# axiom_beta_sensor_cmv12000_tht_v0_16_r1_.net
KiCad netlist of a schematic drawn in EAGLE
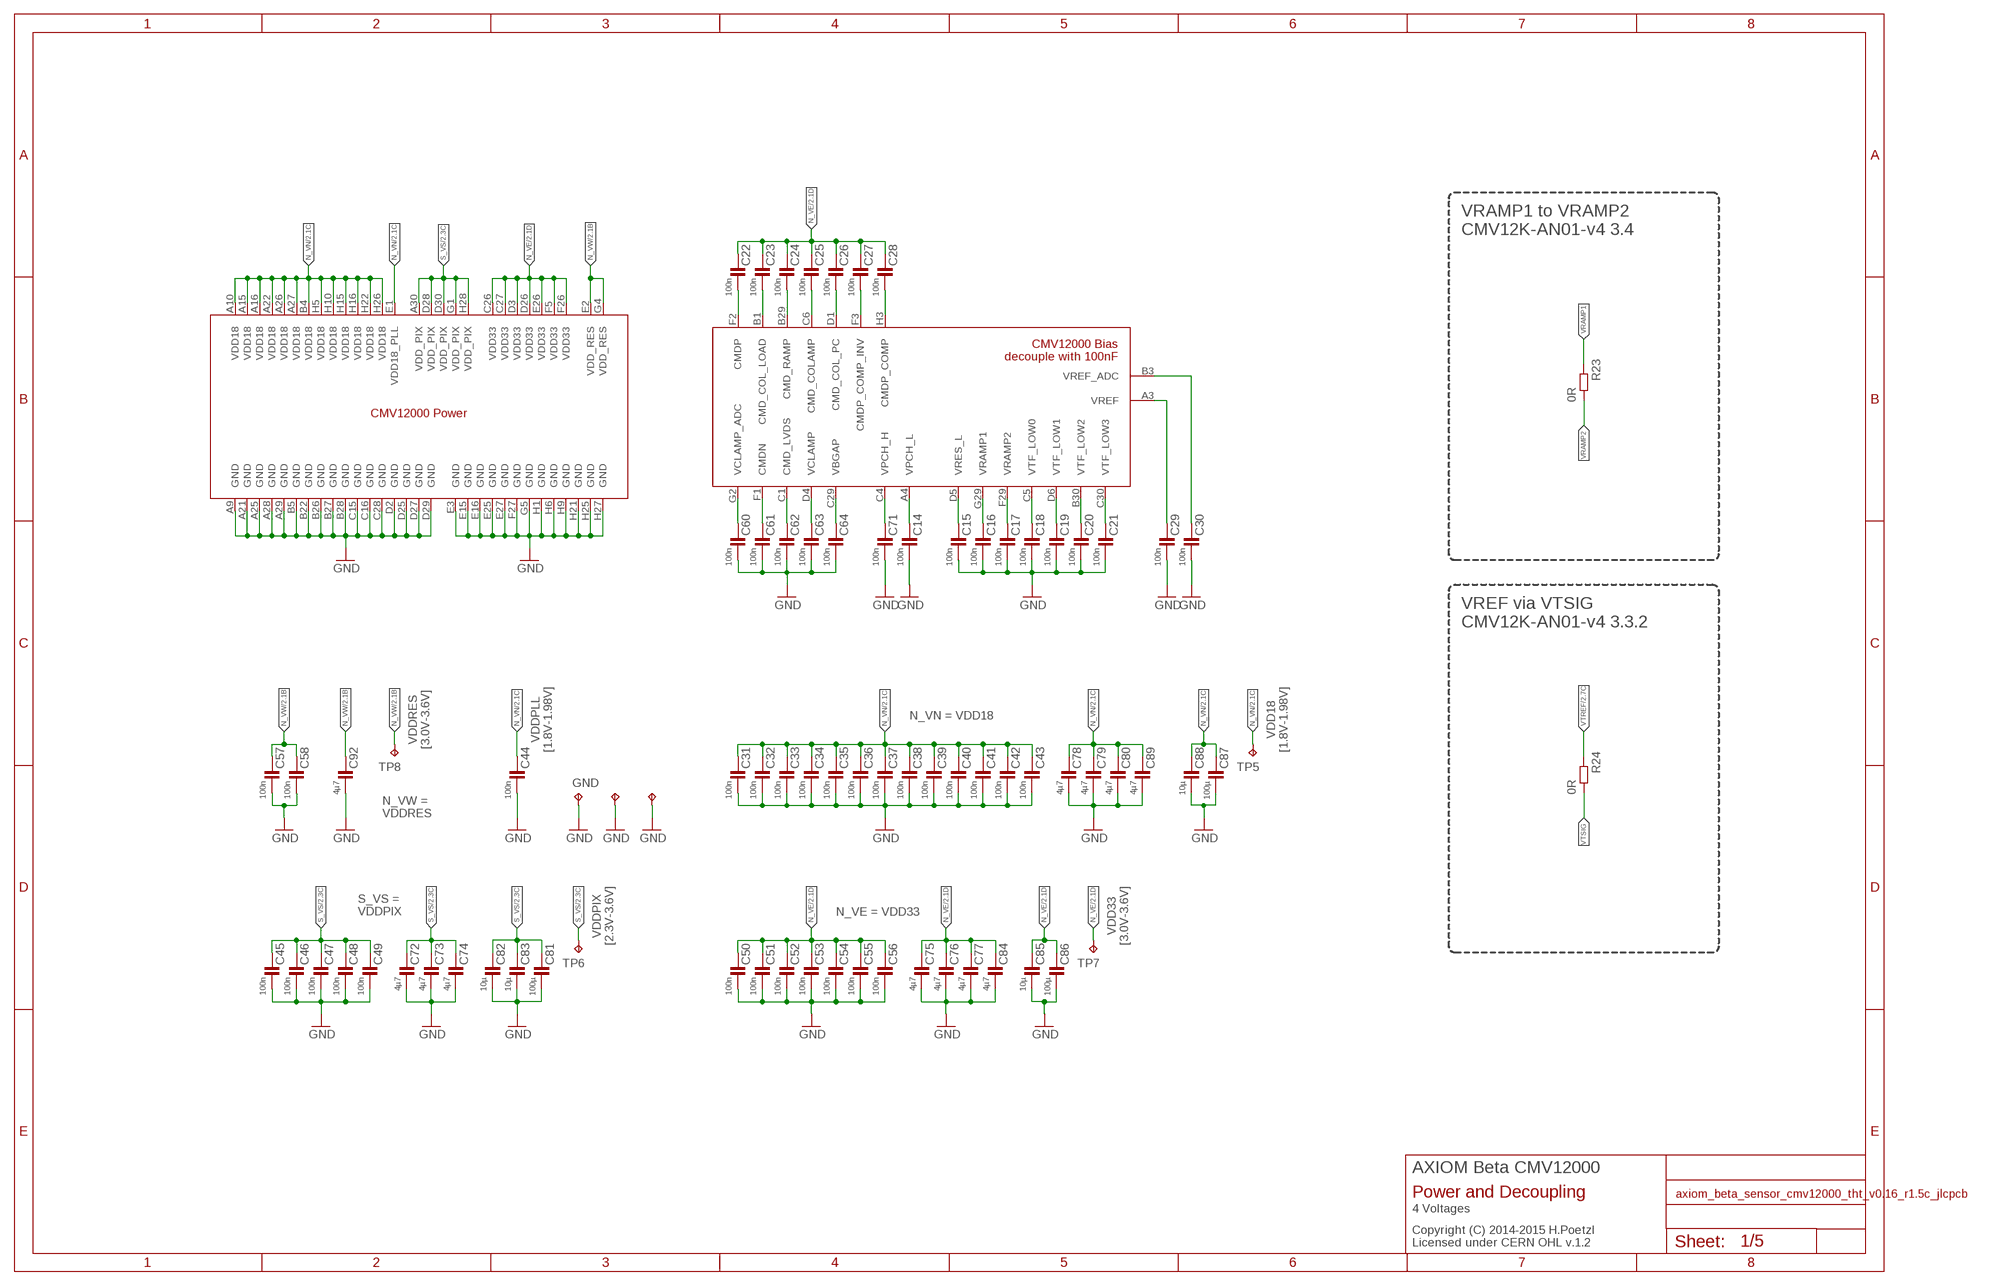
[diagram p0: schematic, sheet 1]
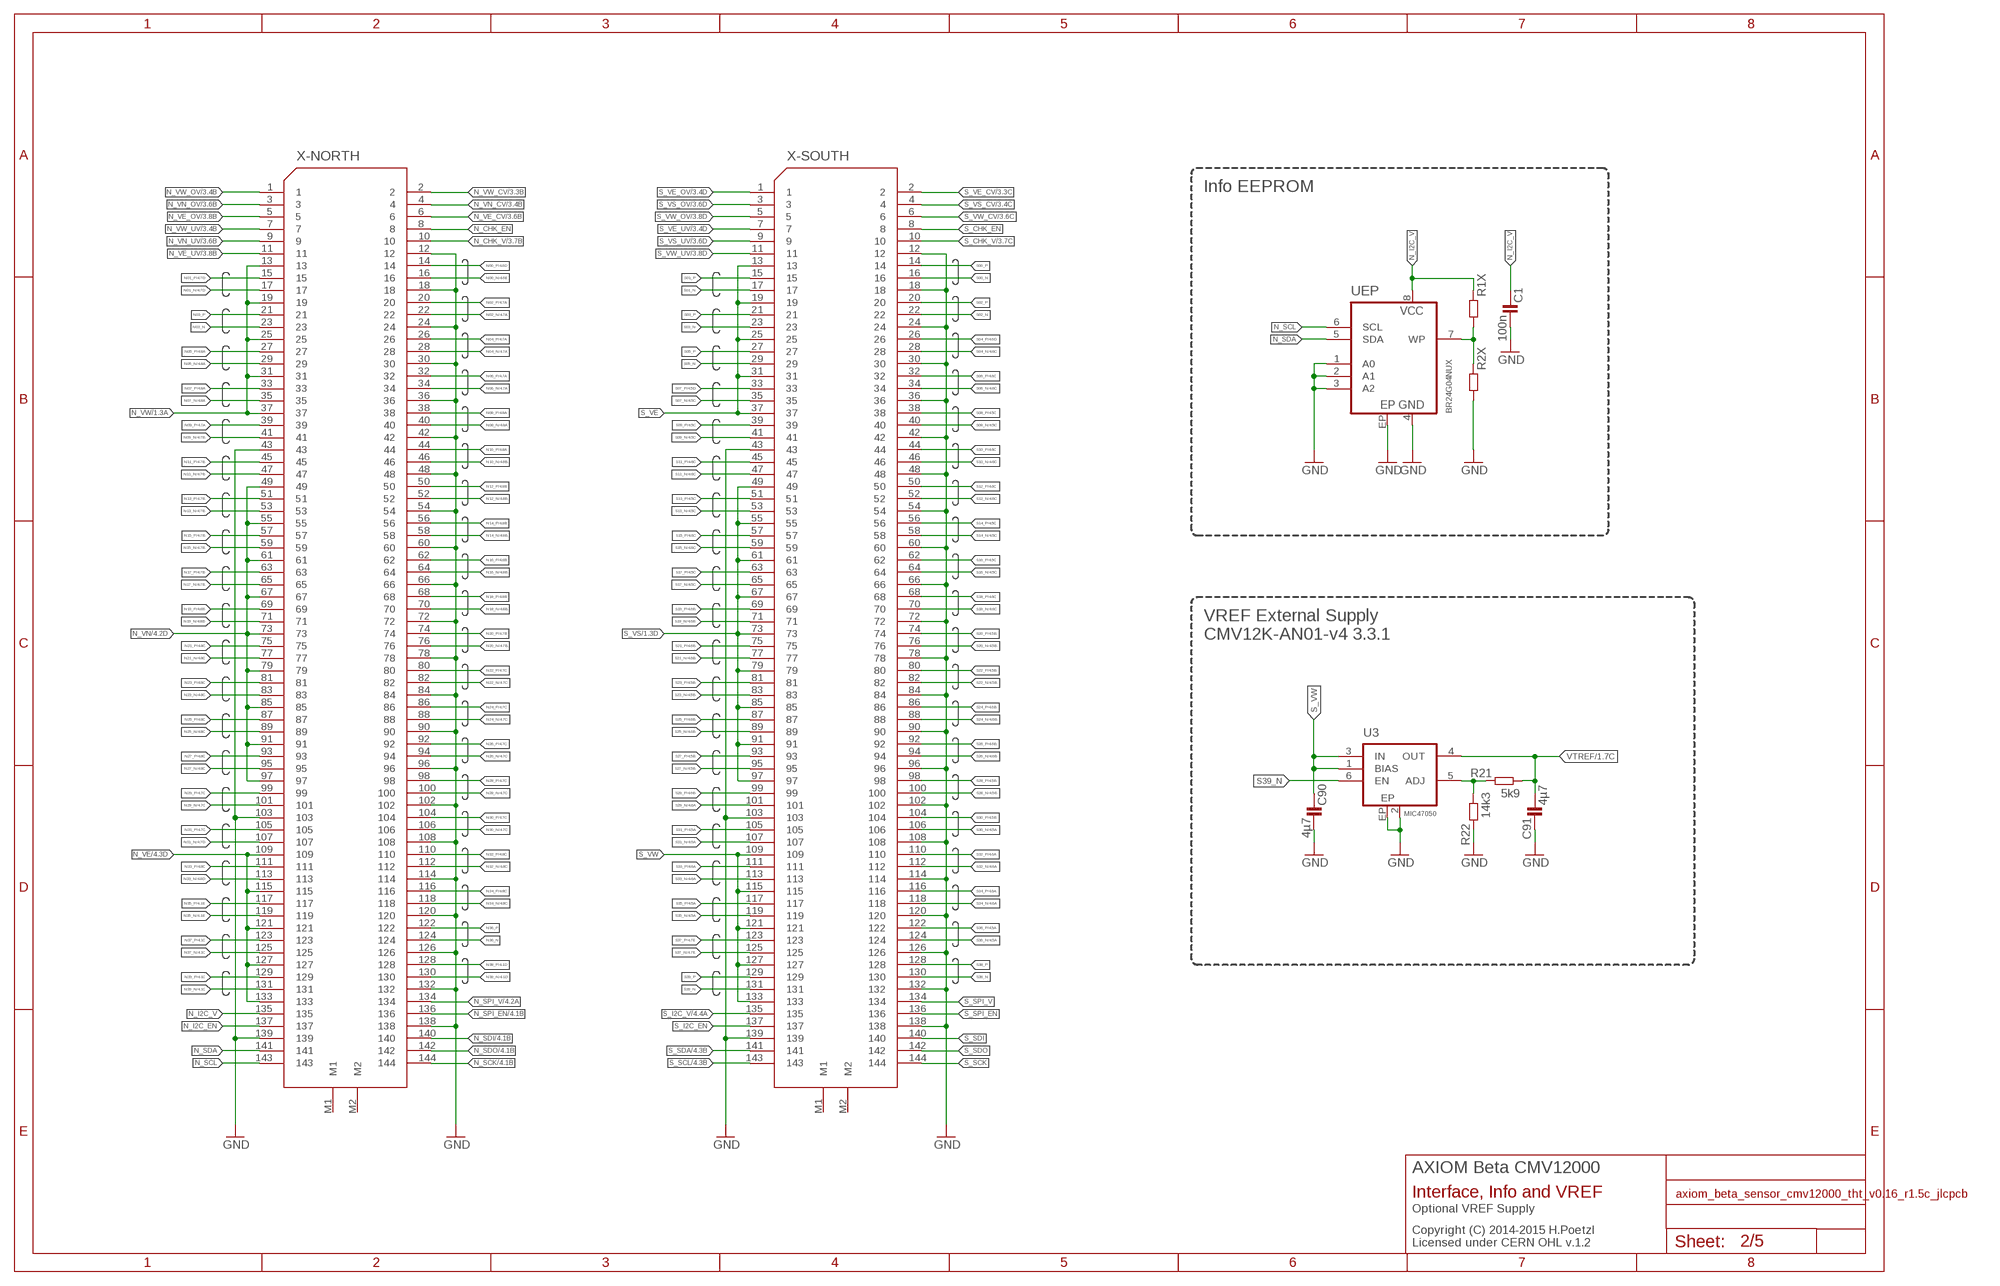
[diagram p1: schematic, sheet 2]
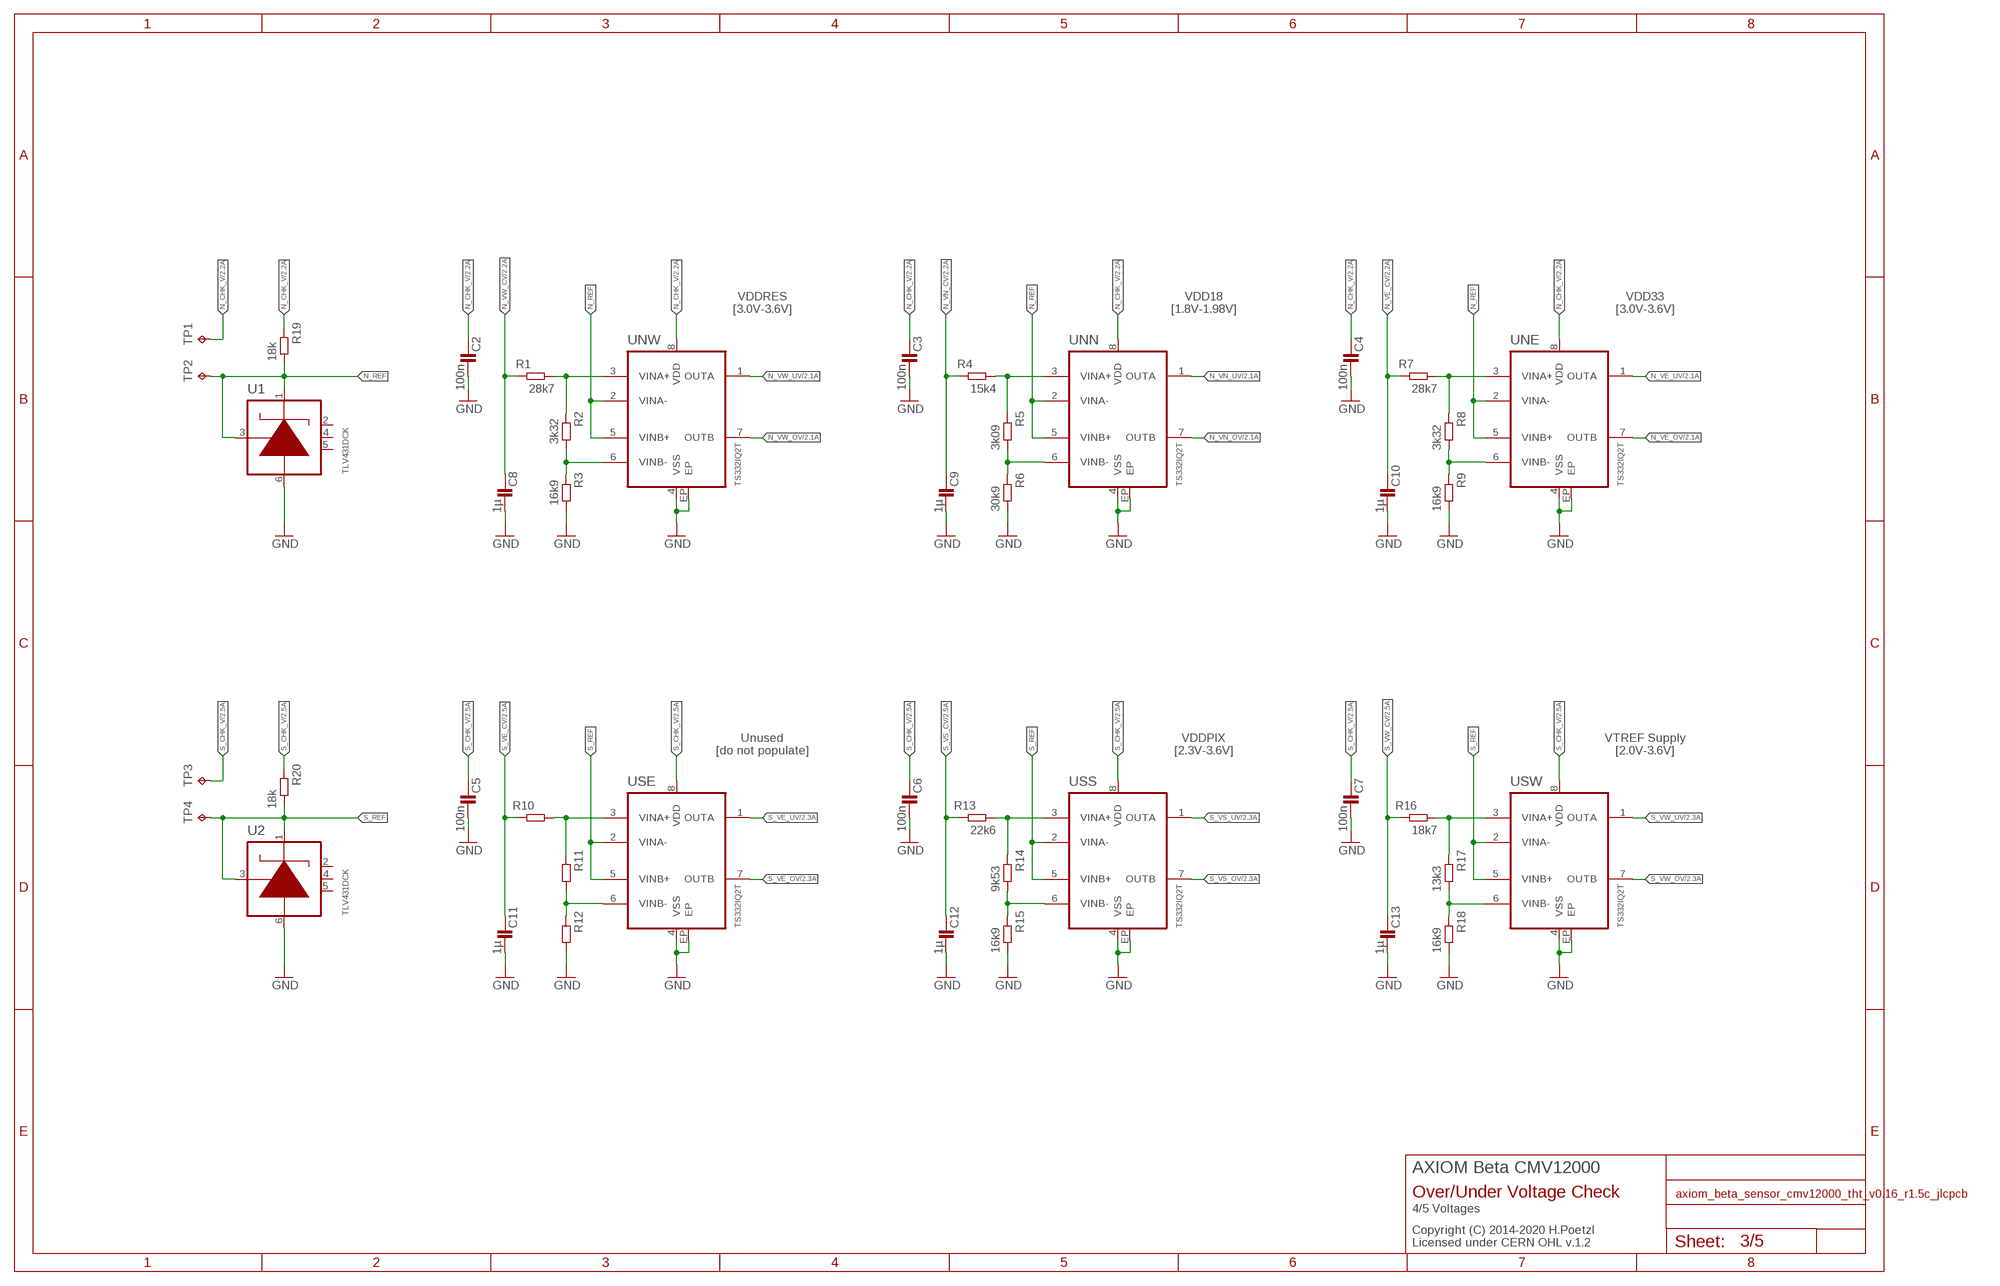
[diagram p2: schematic, sheet 3]
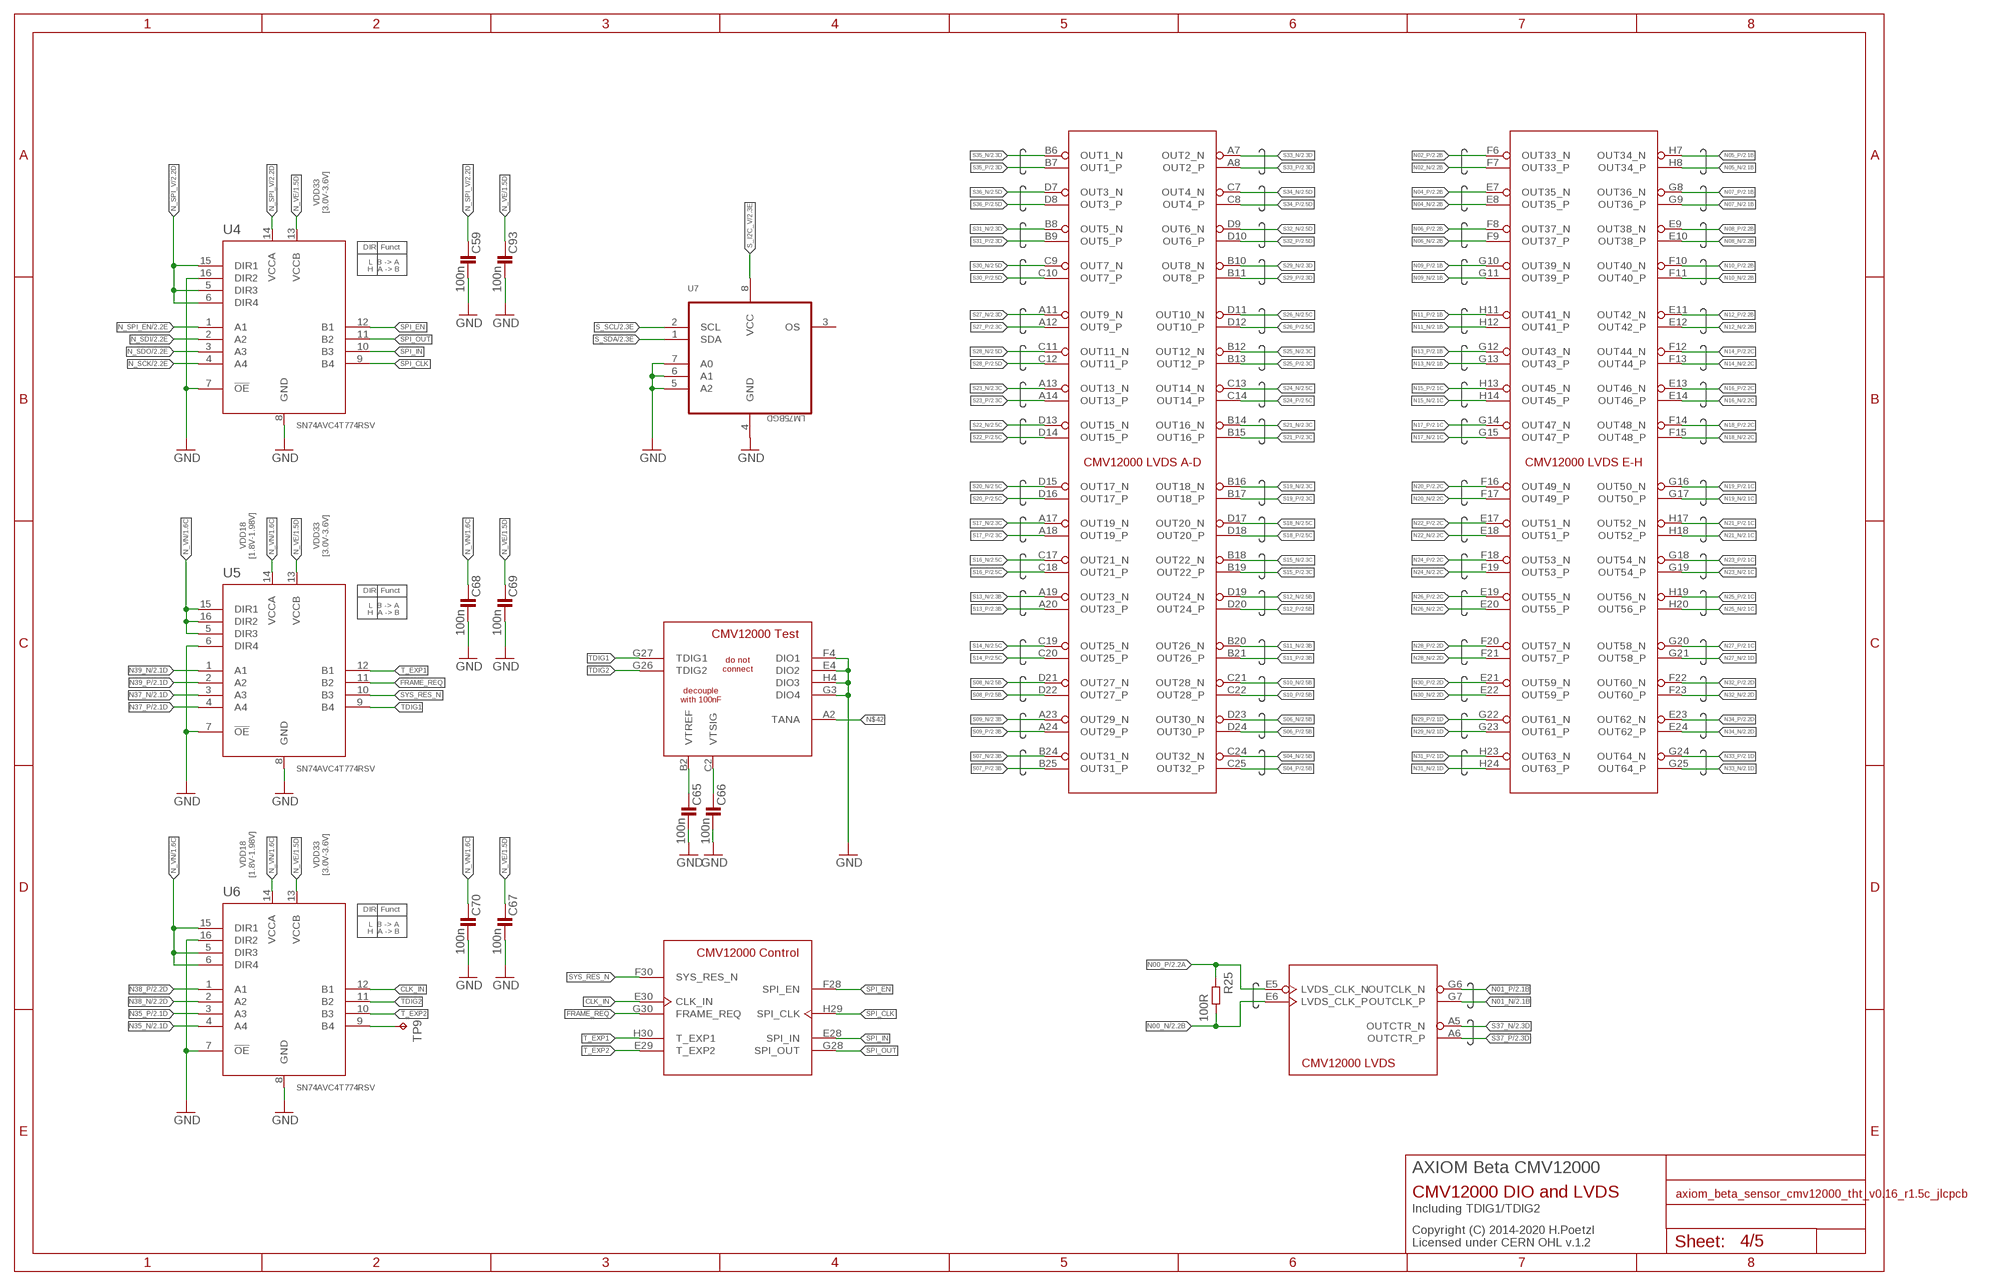
[diagram p3: schematic, sheet 4]
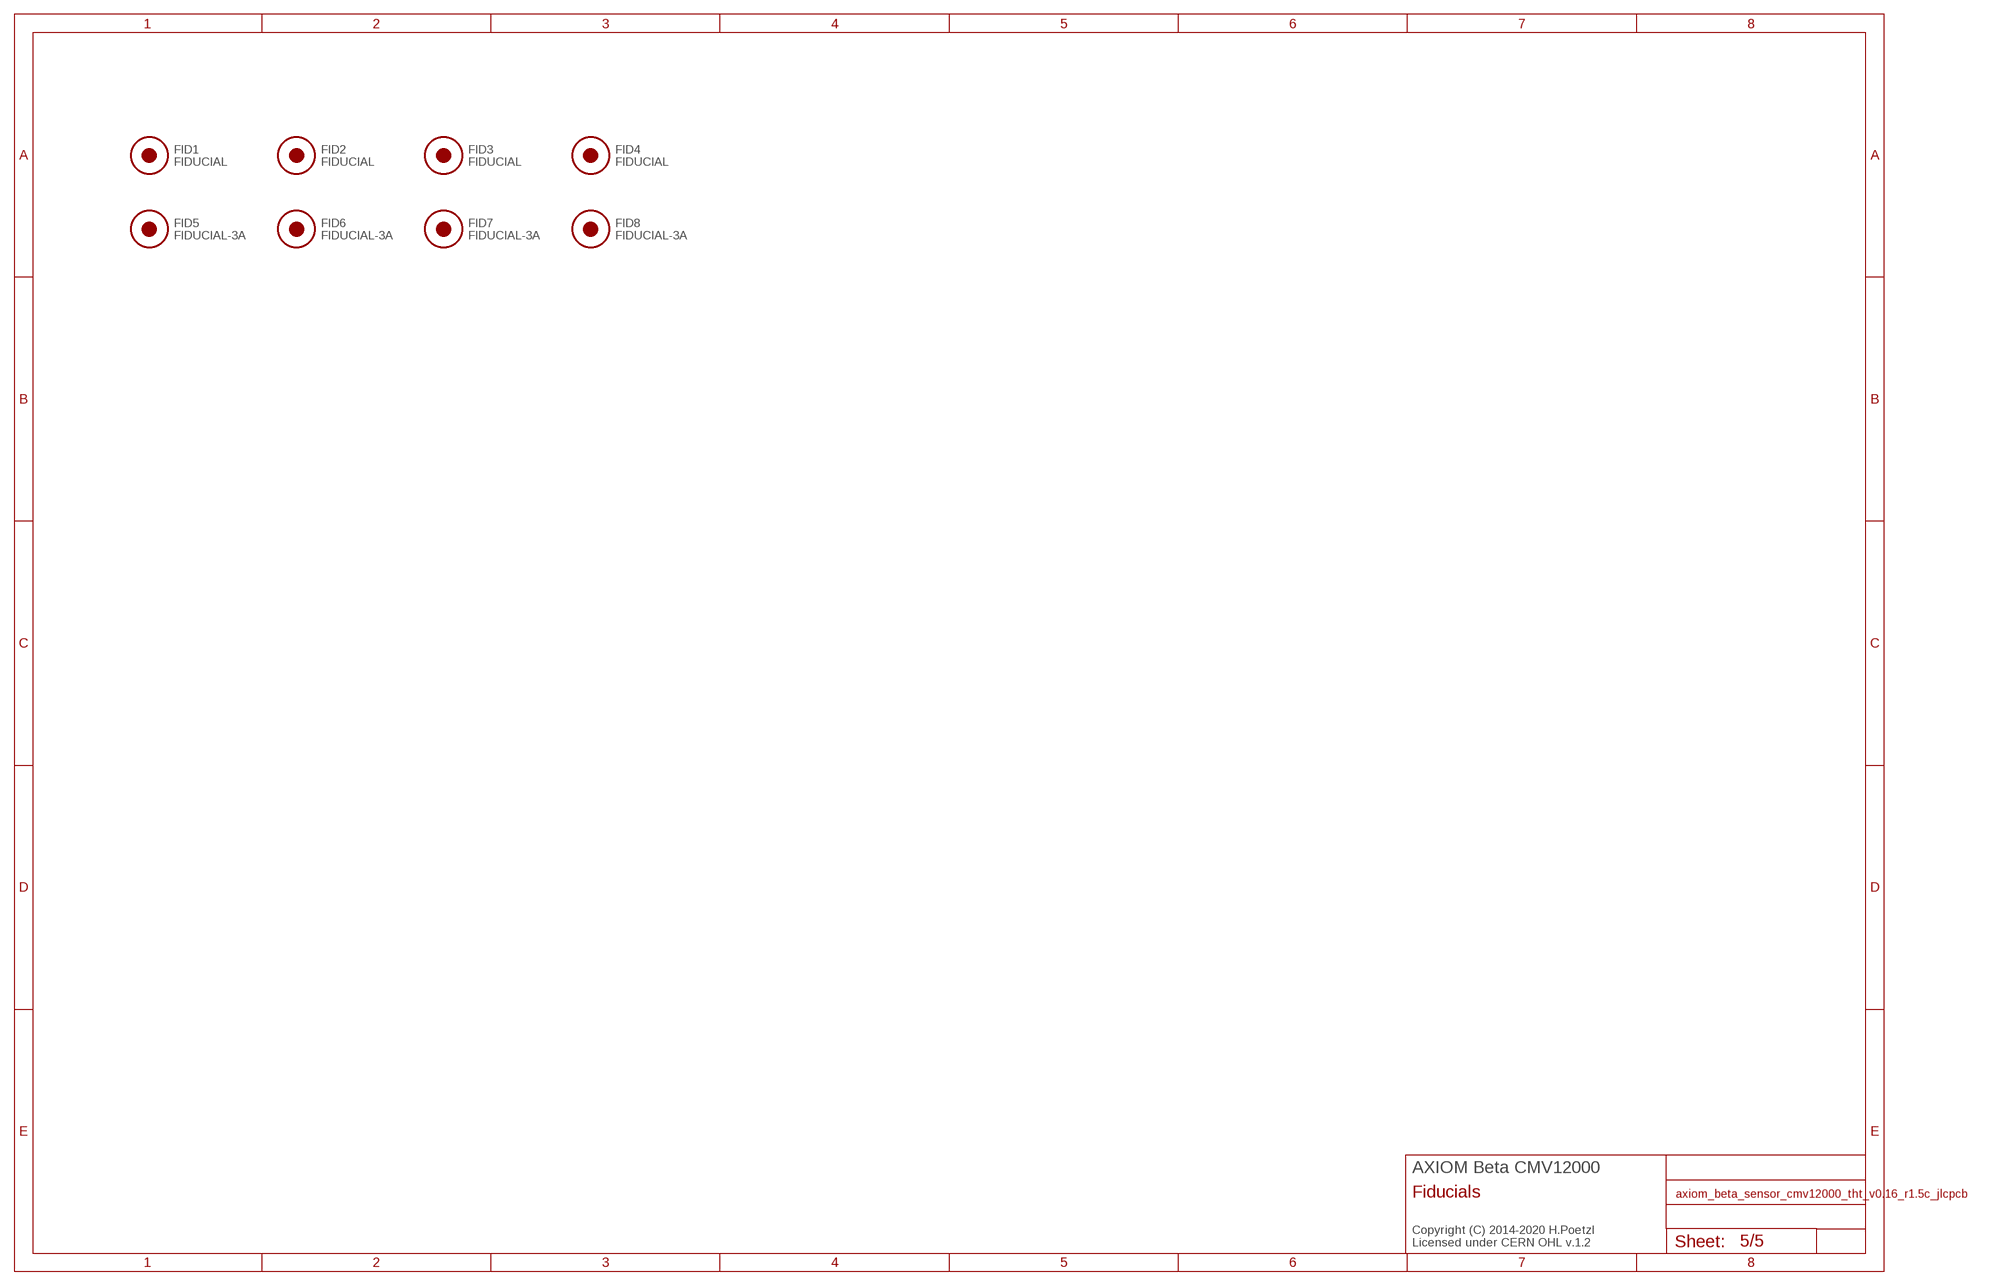
[diagram p4: schematic, sheet 5]

(export (version "E")
  (design (tool "Eeschema 10.0.6"))
  (components
    (comp (ref "FID1")
      (value "FIDUCIAL")
      (footprint "eagle-import:FID_ARROW")
      (libsource (lib "eagle-import") (part "FIDUCIAL"))
    )
    (comp (ref "FID2")
      (value "FIDUCIAL")
      (footprint "eagle-import:FID_ARROW")
      (libsource (lib "eagle-import") (part "FIDUCIAL"))
    )
    (comp (ref "FID3")
      (value "FIDUCIAL")
      (footprint "eagle-import:FID_ARROW")
      (libsource (lib "eagle-import") (part "FIDUCIAL"))
    )
    (comp (ref "FID4")
      (value "FIDUCIAL")
      (footprint "eagle-import:FID_ARROW")
      (libsource (lib "eagle-import") (part "FIDUCIAL"))
    )
    (comp (ref "FID5")
      (value "FIDUCIAL-3A")
      (footprint "eagle-import:FID_3ARROW")
      (libsource (lib "eagle-import") (part "FIDUCIAL-3A"))
    )
    (comp (ref "FID6")
      (value "FIDUCIAL-3A")
      (footprint "eagle-import:FID_3ARROW")
      (libsource (lib "eagle-import") (part "FIDUCIAL-3A"))
    )
    (comp (ref "FID7")
      (value "FIDUCIAL-3A")
      (footprint "eagle-import:FID_3ARROW")
      (libsource (lib "eagle-import") (part "FIDUCIAL-3A"))
    )
    (comp (ref "FID8")
      (value "FIDUCIAL-3A")
      (footprint "eagle-import:FID_3ARROW")
      (libsource (lib "eagle-import") (part "FIDUCIAL-3A"))
    )
    (comp (ref "C2")
      (value "100n")
      (footprint "eagle-import:0402-C")
      (libsource (lib "eagle-import") (part "C0402-C"))
    )
    (comp (ref "C3")
      (value "100n")
      (footprint "eagle-import:0402-C")
      (libsource (lib "eagle-import") (part "C0402-C"))
    )
    (comp (ref "C4")
      (value "100n")
      (footprint "eagle-import:0402-C")
      (libsource (lib "eagle-import") (part "C0402-C"))
    )
    (comp (ref "C5")
      (value "100n")
      (footprint "eagle-import:0402-C")
      (libsource (lib "eagle-import") (part "C0402-C"))
    )
    (comp (ref "C6")
      (value "100n")
      (footprint "eagle-import:0402-C")
      (libsource (lib "eagle-import") (part "C0402-C"))
    )
    (comp (ref "C7")
      (value "100n")
      (footprint "eagle-import:0402-C")
      (libsource (lib "eagle-import") (part "C0402-C"))
    )
    (comp (ref "C8")
      (value "1µ")
      (footprint "eagle-import:0402-C")
      (libsource (lib "eagle-import") (part "C0402-C"))
    )
    (comp (ref "C9")
      (value "1µ")
      (footprint "eagle-import:0402-C")
      (libsource (lib "eagle-import") (part "C0402-C"))
    )
    (comp (ref "C10")
      (value "1µ")
      (footprint "eagle-import:0402-C")
      (libsource (lib "eagle-import") (part "C0402-C"))
    )
    (comp (ref "C11")
      (value "1µ")
      (footprint "eagle-import:0402-C")
      (libsource (lib "eagle-import") (part "C0402-C"))
    )
    (comp (ref "C12")
      (value "1µ")
      (footprint "eagle-import:0402-C")
      (libsource (lib "eagle-import") (part "C0402-C"))
    )
    (comp (ref "C13")
      (value "1µ")
      (footprint "eagle-import:0402-C")
      (libsource (lib "eagle-import") (part "C0402-C"))
    )
    (comp (ref "R1")
      (value "28k7")
      (footprint "eagle-import:0402-C")
      (libsource (lib "eagle-import") (part "R0402-C"))
    )
    (comp (ref "R2")
      (value "3k32")
      (footprint "eagle-import:0402-C")
      (libsource (lib "eagle-import") (part "R0402-C"))
    )
    (comp (ref "R3")
      (value "16k9")
      (footprint "eagle-import:0402-C")
      (libsource (lib "eagle-import") (part "R0402-C"))
    )
    (comp (ref "R4")
      (value "15k4")
      (footprint "eagle-import:0402-C")
      (libsource (lib "eagle-import") (part "R0402-C"))
    )
    (comp (ref "R5")
      (value "3k09")
      (footprint "eagle-import:0402-C")
      (libsource (lib "eagle-import") (part "R0402-C"))
    )
    (comp (ref "R6")
      (value "30k9")
      (footprint "eagle-import:0402-C")
      (libsource (lib "eagle-import") (part "R0402-C"))
    )
    (comp (ref "R7")
      (value "28k7")
      (footprint "eagle-import:0402-C")
      (libsource (lib "eagle-import") (part "R0402-C"))
    )
    (comp (ref "R8")
      (value "3k32")
      (footprint "eagle-import:0402-C")
      (libsource (lib "eagle-import") (part "R0402-C"))
    )
    (comp (ref "R9")
      (value "16k9")
      (footprint "eagle-import:0402-C")
      (libsource (lib "eagle-import") (part "R0402-C"))
    )
    (comp (ref "R10")
      (value "R0402-C")
      (footprint "eagle-import:0402-C")
      (libsource (lib "eagle-import") (part "R0402-C"))
    )
    (comp (ref "R11")
      (value "R0402-C")
      (footprint "eagle-import:0402-C")
      (libsource (lib "eagle-import") (part "R0402-C"))
    )
    (comp (ref "R12")
      (value "R0402-C")
      (footprint "eagle-import:0402-C")
      (libsource (lib "eagle-import") (part "R0402-C"))
    )
    (comp (ref "R13")
      (value "22k6")
      (footprint "eagle-import:0402-C")
      (libsource (lib "eagle-import") (part "R0402-C"))
    )
    (comp (ref "R14")
      (value "9k53")
      (footprint "eagle-import:0402-C")
      (libsource (lib "eagle-import") (part "R0402-C"))
    )
    (comp (ref "R15")
      (value "16k9")
      (footprint "eagle-import:0402-C")
      (libsource (lib "eagle-import") (part "R0402-C"))
    )
    (comp (ref "R16")
      (value "18k7")
      (footprint "eagle-import:0402-C")
      (libsource (lib "eagle-import") (part "R0402-C"))
    )
    (comp (ref "R17")
      (value "13k3")
      (footprint "eagle-import:0402-C")
      (libsource (lib "eagle-import") (part "R0402-C"))
    )
    (comp (ref "R18")
      (value "16k9")
      (footprint "eagle-import:0402-C")
      (libsource (lib "eagle-import") (part "R0402-C"))
    )
    (comp (ref "R19")
      (value "18k")
      (footprint "eagle-import:0402-C")
      (libsource (lib "eagle-import") (part "R0402-C"))
    )
    (comp (ref "R20")
      (value "18k")
      (footprint "eagle-import:0402-C")
      (libsource (lib "eagle-import") (part "R0402-C"))
    )
    (comp (ref "TP1")
      (value "TPTP10R")
      (footprint "eagle-import:TP10R")
      (libsource (lib "eagle-import") (part "TPTP10R"))
    )
    (comp (ref "TP2")
      (value "TPTP10R")
      (footprint "eagle-import:TP10R")
      (libsource (lib "eagle-import") (part "TPTP10R"))
    )
    (comp (ref "TP3")
      (value "TPTP10R")
      (footprint "eagle-import:TP10R")
      (libsource (lib "eagle-import") (part "TPTP10R"))
    )
    (comp (ref "TP4")
      (value "TPTP10R")
      (footprint "eagle-import:TP10R")
      (libsource (lib "eagle-import") (part "TPTP10R"))
    )
    (comp (ref "U1")
      (value "TLV431DCK")
      (footprint "eagle-import:SOT65P210X110-6N")
      (libsource (lib "eagle-import") (part "TLV431DCK"))
    )
    (comp (ref "U2")
      (value "TLV431DCK")
      (footprint "eagle-import:SOT65P210X110-6N")
      (libsource (lib "eagle-import") (part "TLV431DCK"))
    )
    (comp (ref "UNE")
      (value "TS332IQ2T")
      (footprint "eagle-import:DFN200X200X100-9N")
      (libsource (lib "eagle-import") (part "TS332IQ2T"))
    )
    (comp (ref "UNN")
      (value "TS332IQ2T")
      (footprint "eagle-import:DFN200X200X100-9N")
      (libsource (lib "eagle-import") (part "TS332IQ2T"))
    )
    (comp (ref "UNW")
      (value "TS332IQ2T")
      (footprint "eagle-import:DFN200X200X100-9N")
      (libsource (lib "eagle-import") (part "TS332IQ2T"))
    )
    (comp (ref "USE")
      (value "TS332IQ2T")
      (footprint "eagle-import:DFN200X200X100-9N")
      (libsource (lib "eagle-import") (part "TS332IQ2T"))
    )
    (comp (ref "USS")
      (value "TS332IQ2T")
      (footprint "eagle-import:DFN200X200X100-9N")
      (libsource (lib "eagle-import") (part "TS332IQ2T"))
    )
    (comp (ref "USW")
      (value "TS332IQ2T")
      (footprint "eagle-import:DFN200X200X100-9N")
      (libsource (lib "eagle-import") (part "TS332IQ2T"))
    )
    (comp (ref "C14")
      (value "100n")
      (footprint "eagle-import:0402-C")
      (libsource (lib "eagle-import") (part "C0402-C"))
    )
    (comp (ref "C15")
      (value "100n")
      (footprint "eagle-import:0402-C")
      (libsource (lib "eagle-import") (part "C0402-C"))
    )
    (comp (ref "C16")
      (value "100n")
      (footprint "eagle-import:0402-C")
      (libsource (lib "eagle-import") (part "C0402-C"))
    )
    (comp (ref "C17")
      (value "100n")
      (footprint "eagle-import:0402-C")
      (libsource (lib "eagle-import") (part "C0402-C"))
    )
    (comp (ref "C18")
      (value "100n")
      (footprint "eagle-import:0402-C")
      (libsource (lib "eagle-import") (part "C0402-C"))
    )
    (comp (ref "C19")
      (value "100n")
      (footprint "eagle-import:0402-C")
      (libsource (lib "eagle-import") (part "C0402-C"))
    )
    (comp (ref "C20")
      (value "100n")
      (footprint "eagle-import:0402-C")
      (libsource (lib "eagle-import") (part "C0402-C"))
    )
    (comp (ref "C21")
      (value "100n")
      (footprint "eagle-import:0402-C")
      (libsource (lib "eagle-import") (part "C0402-C"))
    )
    (comp (ref "C22")
      (value "100n")
      (footprint "eagle-import:0402-C")
      (libsource (lib "eagle-import") (part "C0402-C"))
    )
    (comp (ref "C23")
      (value "100n")
      (footprint "eagle-import:0402-C")
      (libsource (lib "eagle-import") (part "C0402-C"))
    )
    (comp (ref "C24")
      (value "100n")
      (footprint "eagle-import:0402-C")
      (libsource (lib "eagle-import") (part "C0402-C"))
    )
    (comp (ref "C25")
      (value "100n")
      (footprint "eagle-import:0402-C")
      (libsource (lib "eagle-import") (part "C0402-C"))
    )
    (comp (ref "C26")
      (value "100n")
      (footprint "eagle-import:0402-C")
      (libsource (lib "eagle-import") (part "C0402-C"))
    )
    (comp (ref "C27")
      (value "100n")
      (footprint "eagle-import:0402-C")
      (libsource (lib "eagle-import") (part "C0402-C"))
    )
    (comp (ref "C28")
      (value "100n")
      (footprint "eagle-import:0402-C")
      (libsource (lib "eagle-import") (part "C0402-C"))
    )
    (comp (ref "C29")
      (value "100n")
      (footprint "eagle-import:0402-C")
      (libsource (lib "eagle-import") (part "C0402-C"))
    )
    (comp (ref "C30")
      (value "100n")
      (footprint "eagle-import:0402-C")
      (libsource (lib "eagle-import") (part "C0402-C"))
    )
    (comp (ref "C31")
      (value "100n")
      (footprint "eagle-import:0402-C")
      (libsource (lib "eagle-import") (part "C0402-C"))
    )
    (comp (ref "C32")
      (value "100n")
      (footprint "eagle-import:0402-C")
      (libsource (lib "eagle-import") (part "C0402-C"))
    )
    (comp (ref "C33")
      (value "100n")
      (footprint "eagle-import:0402-C")
      (libsource (lib "eagle-import") (part "C0402-C"))
    )
    (comp (ref "C34")
      (value "100n")
      (footprint "eagle-import:0402-C")
      (libsource (lib "eagle-import") (part "C0402-C"))
    )
    (comp (ref "C35")
      (value "100n")
      (footprint "eagle-import:0402-C")
      (libsource (lib "eagle-import") (part "C0402-C"))
    )
    (comp (ref "C36")
      (value "100n")
      (footprint "eagle-import:0402-C")
      (libsource (lib "eagle-import") (part "C0402-C"))
    )
    (comp (ref "C37")
      (value "100n")
      (footprint "eagle-import:0402-C")
      (libsource (lib "eagle-import") (part "C0402-C"))
    )
    (comp (ref "C38")
      (value "100n")
      (footprint "eagle-import:0402-C")
      (libsource (lib "eagle-import") (part "C0402-C"))
    )
    (comp (ref "C39")
      (value "100n")
      (footprint "eagle-import:0402-C")
      (libsource (lib "eagle-import") (part "C0402-C"))
    )
    (comp (ref "C40")
      (value "100n")
      (footprint "eagle-import:0402-C")
      (libsource (lib "eagle-import") (part "C0402-C"))
    )
    (comp (ref "C41")
      (value "100n")
      (footprint "eagle-import:0402-C")
      (libsource (lib "eagle-import") (part "C0402-C"))
    )
    (comp (ref "C42")
      (value "100n")
      (footprint "eagle-import:0402-C")
      (libsource (lib "eagle-import") (part "C0402-C"))
    )
    (comp (ref "C43")
      (value "100n")
      (footprint "eagle-import:0402-C")
      (libsource (lib "eagle-import") (part "C0402-C"))
    )
    (comp (ref "C44")
      (value "100n")
      (footprint "eagle-import:0402-C")
      (libsource (lib "eagle-import") (part "C0402-C"))
    )
    (comp (ref "C45")
      (value "100n")
      (footprint "eagle-import:0402-C")
      (libsource (lib "eagle-import") (part "C0402-C"))
    )
    (comp (ref "C46")
      (value "100n")
      (footprint "eagle-import:0402-C")
      (libsource (lib "eagle-import") (part "C0402-C"))
    )
    (comp (ref "C47")
      (value "100n")
      (footprint "eagle-import:0402-C")
      (libsource (lib "eagle-import") (part "C0402-C"))
    )
    (comp (ref "C48")
      (value "100n")
      (footprint "eagle-import:0402-C")
      (libsource (lib "eagle-import") (part "C0402-C"))
    )
    (comp (ref "C49")
      (value "100n")
      (footprint "eagle-import:0402-C")
      (libsource (lib "eagle-import") (part "C0402-C"))
    )
    (comp (ref "C50")
      (value "100n")
      (footprint "eagle-import:0402-C")
      (libsource (lib "eagle-import") (part "C0402-C"))
    )
    (comp (ref "C51")
      (value "100n")
      (footprint "eagle-import:0402-C")
      (libsource (lib "eagle-import") (part "C0402-C"))
    )
    (comp (ref "C52")
      (value "100n")
      (footprint "eagle-import:0402-C")
      (libsource (lib "eagle-import") (part "C0402-C"))
    )
    (comp (ref "C53")
      (value "100n")
      (footprint "eagle-import:0402-C")
      (libsource (lib "eagle-import") (part "C0402-C"))
    )
    (comp (ref "C54")
      (value "100n")
      (footprint "eagle-import:0402-C")
      (libsource (lib "eagle-import") (part "C0402-C"))
    )
    (comp (ref "C55")
      (value "100n")
      (footprint "eagle-import:0402-C")
      (libsource (lib "eagle-import") (part "C0402-C"))
    )
    (comp (ref "C56")
      (value "100n")
      (footprint "eagle-import:0402-C")
      (libsource (lib "eagle-import") (part "C0402-C"))
    )
    (comp (ref "C57")
      (value "100n")
      (footprint "eagle-import:0402-C")
      (libsource (lib "eagle-import") (part "C0402-C"))
    )
    (comp (ref "C58")
      (value "100n")
      (footprint "eagle-import:0402-C")
      (libsource (lib "eagle-import") (part "C0402-C"))
    )
    (comp (ref "C60")
      (value "100n")
      (footprint "eagle-import:0402-C")
      (libsource (lib "eagle-import") (part "C0402-C"))
    )
    (comp (ref "C61")
      (value "100n")
      (footprint "eagle-import:0402-C")
      (libsource (lib "eagle-import") (part "C0402-C"))
    )
    (comp (ref "C62")
      (value "100n")
      (footprint "eagle-import:0402-C")
      (libsource (lib "eagle-import") (part "C0402-C"))
    )
    (comp (ref "C63")
      (value "100n")
      (footprint "eagle-import:0402-C")
      (libsource (lib "eagle-import") (part "C0402-C"))
    )
    (comp (ref "C64")
      (value "100n")
      (footprint "eagle-import:0402-C")
      (libsource (lib "eagle-import") (part "C0402-C"))
    )
    (comp (ref "C71")
      (value "100n")
      (footprint "eagle-import:0402-C")
      (libsource (lib "eagle-import") (part "C0402-C"))
    )
    (comp (ref "C72")
      (value "4µ7")
      (footprint "eagle-import:0402-B")
      (libsource (lib "eagle-import") (part "C0402-B"))
    )
    (comp (ref "C73")
      (value "4µ7")
      (footprint "eagle-import:0402-C")
      (libsource (lib "eagle-import") (part "C0402-C"))
    )
    (comp (ref "C74")
      (value "4µ7")
      (footprint "eagle-import:0402-C")
      (libsource (lib "eagle-import") (part "C0402-C"))
    )
    (comp (ref "C75")
      (value "4µ7")
      (footprint "eagle-import:0402-C")
      (libsource (lib "eagle-import") (part "C0402-C"))
    )
    (comp (ref "C76")
      (value "4µ7")
      (footprint "eagle-import:0402-C")
      (libsource (lib "eagle-import") (part "C0402-C"))
    )
    (comp (ref "C77")
      (value "4µ7")
      (footprint "eagle-import:0402-B")
      (libsource (lib "eagle-import") (part "C0402-B"))
    )
    (comp (ref "C78")
      (value "4µ7")
      (footprint "eagle-import:0402-B")
      (libsource (lib "eagle-import") (part "C0402-B"))
    )
    (comp (ref "C79")
      (value "4µ7")
      (footprint "eagle-import:0402-C")
      (libsource (lib "eagle-import") (part "C0402-C"))
    )
    (comp (ref "C80")
      (value "4µ7")
      (footprint "eagle-import:0402-C")
      (libsource (lib "eagle-import") (part "C0402-C"))
    )
    (comp (ref "C81")
      (value "100µ")
      (footprint "eagle-import:1206-B")
      (libsource (lib "eagle-import") (part "C1206-B"))
    )
    (comp (ref "C82")
      (value "10µ")
      (footprint "eagle-import:0603-C")
      (libsource (lib "eagle-import") (part "C0603-C"))
    )
    (comp (ref "C83")
      (value "10µ")
      (footprint "eagle-import:0603-C")
      (libsource (lib "eagle-import") (part "C0603-C"))
    )
    (comp (ref "C84")
      (value "4µ7")
      (footprint "eagle-import:0402-C")
      (libsource (lib "eagle-import") (part "C0402-C"))
    )
    (comp (ref "C85")
      (value "10µ")
      (footprint "eagle-import:0603-C")
      (libsource (lib "eagle-import") (part "C0603-C"))
    )
    (comp (ref "C86")
      (value "100µ")
      (footprint "eagle-import:1206-B")
      (libsource (lib "eagle-import") (part "C1206-B"))
    )
    (comp (ref "C87")
      (value "100µ")
      (footprint "eagle-import:1206-B")
      (libsource (lib "eagle-import") (part "C1206-B"))
    )
    (comp (ref "C88")
      (value "10µ")
      (footprint "eagle-import:0603-C")
      (libsource (lib "eagle-import") (part "C0603-C"))
    )
    (comp (ref "C89")
      (value "4µ7")
      (footprint "eagle-import:0402-C")
      (libsource (lib "eagle-import") (part "C0402-C"))
    )
    (comp (ref "C92")
      (value "4µ7")
      (footprint "eagle-import:0402-C")
      (libsource (lib "eagle-import") (part "C0402-C"))
    )
    (comp (ref "GND")
      (value "TPTP10R")
      (footprint "eagle-import:TP10R")
      (libsource (lib "eagle-import") (part "TPTP10R"))
    )
    (comp (ref "GND75")
      (value "TPTP10R")
      (footprint "eagle-import:TP10R")
      (libsource (lib "eagle-import") (part "TPTP10R"))
    )
    (comp (ref "GND77")
      (value "TPTP10R")
      (footprint "eagle-import:TP10R")
      (libsource (lib "eagle-import") (part "TPTP10R"))
    )
    (comp (ref "R23")
      (value "0R")
      (footprint "eagle-import:0402-C")
      (libsource (lib "eagle-import") (part "R0402-C"))
    )
    (comp (ref "R24")
      (value "0R")
      (footprint "eagle-import:0402-C")
      (libsource (lib "eagle-import") (part "R0402-C"))
    )
    (comp (ref "SENSOR")
      (value "CMV12000JLCPCB")
      (footprint "eagle-import:10-30-07-237-400T4-JLCPCB")
      (libsource (lib "eagle-import") (part "CMV12000JLCPCB"))
    )
    (comp (ref "TP5")
      (value "TPTP10R")
      (footprint "eagle-import:TP10R")
      (libsource (lib "eagle-import") (part "TPTP10R"))
    )
    (comp (ref "TP6")
      (value "TPTP10R")
      (footprint "eagle-import:TP10R")
      (libsource (lib "eagle-import") (part "TPTP10R"))
    )
    (comp (ref "TP7")
      (value "TPTP10R")
      (footprint "eagle-import:TP10R")
      (libsource (lib "eagle-import") (part "TPTP10R"))
    )
    (comp (ref "TP8")
      (value "TPTP10R")
      (footprint "eagle-import:TP10R")
      (libsource (lib "eagle-import") (part "TPTP10R"))
    )
    (comp (ref "C59")
      (value "100n")
      (footprint "eagle-import:0402-C")
      (libsource (lib "eagle-import") (part "C0402-C"))
    )
    (comp (ref "C65")
      (value "100n")
      (footprint "eagle-import:0402-C")
      (libsource (lib "eagle-import") (part "C0402-C"))
    )
    (comp (ref "C66")
      (value "100n")
      (footprint "eagle-import:0402-C")
      (libsource (lib "eagle-import") (part "C0402-C"))
    )
    (comp (ref "C67")
      (value "100n")
      (footprint "eagle-import:0402-C")
      (libsource (lib "eagle-import") (part "C0402-C"))
    )
    (comp (ref "C68")
      (value "100n")
      (footprint "eagle-import:0402-C")
      (libsource (lib "eagle-import") (part "C0402-C"))
    )
    (comp (ref "C69")
      (value "100n")
      (footprint "eagle-import:0402-C")
      (libsource (lib "eagle-import") (part "C0402-C"))
    )
    (comp (ref "C70")
      (value "100n")
      (footprint "eagle-import:0402-C")
      (libsource (lib "eagle-import") (part "C0402-C"))
    )
    (comp (ref "C93")
      (value "100n")
      (footprint "eagle-import:0402-C")
      (libsource (lib "eagle-import") (part "C0402-C"))
    )
    (comp (ref "R25")
      (value "100R")
      (footprint "eagle-import:0402-C")
      (libsource (lib "eagle-import") (part "R0402-C"))
    )
    (comp (ref "TP9")
      (value "TPTP10R")
      (footprint "eagle-import:TP10R")
      (libsource (lib "eagle-import") (part "TPTP10R"))
    )
    (comp (ref "U4")
      (value "SN74AVC4T774RSV")
      (footprint "eagle-import:QFN40P185X265X55-16N")
      (libsource (lib "eagle-import") (part "SN74AVC4T774RSV"))
    )
    (comp (ref "U5")
      (value "SN74AVC4T774RSV")
      (footprint "eagle-import:QFN40P185X265X55-16N")
      (libsource (lib "eagle-import") (part "SN74AVC4T774RSV"))
    )
    (comp (ref "U6")
      (value "SN74AVC4T774RSV")
      (footprint "eagle-import:QFN40P185X265X55-16N")
      (libsource (lib "eagle-import") (part "SN74AVC4T774RSV"))
    )
    (comp (ref "U7")
      (value "LM75BGD")
      (footprint "eagle-import:SOT996-2_3")
      (libsource (lib "eagle-import") (part "LM75BGD"))
    )
    (comp (ref "C1")
      (value "100n")
      (footprint "eagle-import:0402-C")
      (libsource (lib "eagle-import") (part "C0402-C"))
    )
    (comp (ref "C90")
      (value "4µ7")
      (footprint "eagle-import:0402-C")
      (libsource (lib "eagle-import") (part "C0402-C"))
    )
    (comp (ref "C91")
      (value "4µ7")
      (footprint "eagle-import:0402-C")
      (libsource (lib "eagle-import") (part "C0402-C"))
    )
    (comp (ref "R1X")
      (value "R0402-C")
      (footprint "eagle-import:0402-C")
      (libsource (lib "eagle-import") (part "R0402-C"))
    )
    (comp (ref "R2X")
      (value "R0402-C")
      (footprint "eagle-import:0402-C")
      (libsource (lib "eagle-import") (part "R0402-C"))
    )
    (comp (ref "R21")
      (value "5k9")
      (footprint "eagle-import:0402-C")
      (libsource (lib "eagle-import") (part "R0402-C"))
    )
    (comp (ref "R22")
      (value "14k3")
      (footprint "eagle-import:0402-C")
      (libsource (lib "eagle-import") (part "R0402-C"))
    )
    (comp (ref "U3")
      (value "MIC47050")
      (footprint "eagle-import:MLF-6")
      (libsource (lib "eagle-import") (part "MIC47050-ADJ"))
    )
    (comp (ref "UEP")
      (value "BR24G04NUX")
      (footprint "eagle-import:DFN200X300X100-9N")
      (libsource (lib "eagle-import") (part "BR24G04NUX"))
    )
    (comp (ref "X-NORTH")
      (value "FX10-144P")
      (footprint "eagle-import:FX10A-144P")
      (libsource (lib "eagle-import") (part "FX10-144P"))
    )
    (comp (ref "X-SOUTH")
      (value "FX10-144P")
      (footprint "eagle-import:FX10A-144P")
      (libsource (lib "eagle-import") (part "FX10-144P"))
    )
  )
  (nets
    (net (code "1") (name "CLK_IN") (class "Default")
      (node (ref "SENSOR") (pin "E30") (pinfunction "CLK_IN_E30") (pintype "input"))
      (node (ref "U6") (pin "12") (pinfunction "B1_12") (pintype "bidirectional"))
    )
    (net (code "2") (name "FRAME_REQ") (class "Default")
      (node (ref "SENSOR") (pin "G30") (pinfunction "FRAME_REQ_G30") (pintype "input"))
      (node (ref "U5") (pin "11") (pinfunction "B2_11") (pintype "bidirectional"))
    )
    (net (code "3") (name "GND") (class "Default")
      (node (ref "C1") (pin "2") (pinfunction "2_2") (pintype "passive"))
      (node (ref "C10") (pin "2") (pinfunction "2_2") (pintype "passive"))
      (node (ref "C11") (pin "2") (pinfunction "2_2") (pintype "passive"))
      (node (ref "C12") (pin "2") (pinfunction "2_2") (pintype "passive"))
      (node (ref "C13") (pin "2") (pinfunction "2_2") (pintype "passive"))
      (node (ref "C14") (pin "2") (pinfunction "2_2") (pintype "passive"))
      (node (ref "C15") (pin "2") (pinfunction "2_2") (pintype "passive"))
      (node (ref "C16") (pin "2") (pinfunction "2_2") (pintype "passive"))
      (node (ref "C17") (pin "2") (pinfunction "2_2") (pintype "passive"))
      (node (ref "C18") (pin "2") (pinfunction "2_2") (pintype "passive"))
      (node (ref "C19") (pin "2") (pinfunction "2_2") (pintype "passive"))
      (node (ref "C2") (pin "2") (pinfunction "2_2") (pintype "passive"))
      (node (ref "C20") (pin "2") (pinfunction "2_2") (pintype "passive"))
      (node (ref "C21") (pin "2") (pinfunction "2_2") (pintype "passive"))
      (node (ref "C29") (pin "2") (pinfunction "2_2") (pintype "passive"))
      (node (ref "C3") (pin "2") (pinfunction "2_2") (pintype "passive"))
      (node (ref "C30") (pin "2") (pinfunction "2_2") (pintype "passive"))
      (node (ref "C31") (pin "2") (pinfunction "2_2") (pintype "passive"))
      (node (ref "C32") (pin "2") (pinfunction "2_2") (pintype "passive"))
      (node (ref "C33") (pin "2") (pinfunction "2_2") (pintype "passive"))
      (node (ref "C34") (pin "2") (pinfunction "2_2") (pintype "passive"))
      (node (ref "C35") (pin "2") (pinfunction "2_2") (pintype "passive"))
      (node (ref "C36") (pin "2") (pinfunction "2_2") (pintype "passive"))
      (node (ref "C37") (pin "2") (pinfunction "2_2") (pintype "passive"))
      (node (ref "C38") (pin "2") (pinfunction "2_2") (pintype "passive"))
      (node (ref "C39") (pin "2") (pinfunction "2_2") (pintype "passive"))
      (node (ref "C4") (pin "2") (pinfunction "2_2") (pintype "passive"))
      (node (ref "C40") (pin "2") (pinfunction "2_2") (pintype "passive"))
      (node (ref "C41") (pin "2") (pinfunction "2_2") (pintype "passive"))
      (node (ref "C42") (pin "2") (pinfunction "2_2") (pintype "passive"))
      (node (ref "C43") (pin "2") (pinfunction "2_2") (pintype "passive"))
      (node (ref "C44") (pin "2") (pinfunction "2_2") (pintype "passive"))
      (node (ref "C45") (pin "2") (pinfunction "2_2") (pintype "passive"))
      (node (ref "C46") (pin "2") (pinfunction "2_2") (pintype "passive"))
      (node (ref "C47") (pin "2") (pinfunction "2_2") (pintype "passive"))
      (node (ref "C48") (pin "2") (pinfunction "2_2") (pintype "passive"))
      (node (ref "C49") (pin "2") (pinfunction "2_2") (pintype "passive"))
      (node (ref "C5") (pin "2") (pinfunction "2_2") (pintype "passive"))
      (node (ref "C50") (pin "2") (pinfunction "2_2") (pintype "passive"))
      (node (ref "C51") (pin "2") (pinfunction "2_2") (pintype "passive"))
      (node (ref "C52") (pin "2") (pinfunction "2_2") (pintype "passive"))
      (node (ref "C53") (pin "2") (pinfunction "2_2") (pintype "passive"))
      (node (ref "C54") (pin "2") (pinfunction "2_2") (pintype "passive"))
      (node (ref "C55") (pin "2") (pinfunction "2_2") (pintype "passive"))
      (node (ref "C56") (pin "2") (pinfunction "2_2") (pintype "passive"))
      (node (ref "C57") (pin "2") (pinfunction "2_2") (pintype "passive"))
      (node (ref "C58") (pin "2") (pinfunction "2_2") (pintype "passive"))
      (node (ref "C59") (pin "2") (pinfunction "2_2") (pintype "passive"))
      (node (ref "C6") (pin "2") (pinfunction "2_2") (pintype "passive"))
      (node (ref "C60") (pin "2") (pinfunction "2_2") (pintype "passive"))
      (node (ref "C61") (pin "2") (pinfunction "2_2") (pintype "passive"))
      (node (ref "C62") (pin "2") (pinfunction "2_2") (pintype "passive"))
      (node (ref "C63") (pin "2") (pinfunction "2_2") (pintype "passive"))
      (node (ref "C64") (pin "2") (pinfunction "2_2") (pintype "passive"))
      (node (ref "C65") (pin "2") (pinfunction "2_2") (pintype "passive"))
      (node (ref "C66") (pin "2") (pinfunction "2_2") (pintype "passive"))
      (node (ref "C67") (pin "2") (pinfunction "2_2") (pintype "passive"))
      (node (ref "C68") (pin "2") (pinfunction "2_2") (pintype "passive"))
      (node (ref "C69") (pin "2") (pinfunction "2_2") (pintype "passive"))
      (node (ref "C7") (pin "2") (pinfunction "2_2") (pintype "passive"))
      (node (ref "C70") (pin "2") (pinfunction "2_2") (pintype "passive"))
      (node (ref "C71") (pin "2") (pinfunction "2_2") (pintype "passive"))
      (node (ref "C72") (pin "2") (pinfunction "2_2") (pintype "passive"))
      (node (ref "C73") (pin "2") (pinfunction "2_2") (pintype "passive"))
      (node (ref "C74") (pin "2") (pinfunction "2_2") (pintype "passive"))
      (node (ref "C75") (pin "2") (pinfunction "2_2") (pintype "passive"))
      (node (ref "C76") (pin "2") (pinfunction "2_2") (pintype "passive"))
      (node (ref "C77") (pin "2") (pinfunction "2_2") (pintype "passive"))
      (node (ref "C78") (pin "2") (pinfunction "2_2") (pintype "passive"))
      (node (ref "C79") (pin "2") (pinfunction "2_2") (pintype "passive"))
      (node (ref "C8") (pin "2") (pinfunction "2_2") (pintype "passive"))
      (node (ref "C80") (pin "2") (pinfunction "2_2") (pintype "passive"))
      (node (ref "C81") (pin "2") (pinfunction "2_2") (pintype "passive"))
      (node (ref "C82") (pin "2") (pinfunction "2_2") (pintype "passive"))
      (node (ref "C83") (pin "2") (pinfunction "2_2") (pintype "passive"))
      (node (ref "C84") (pin "2") (pinfunction "2_2") (pintype "passive"))
      (node (ref "C85") (pin "2") (pinfunction "2_2") (pintype "passive"))
      (node (ref "C86") (pin "2") (pinfunction "2_2") (pintype "passive"))
      (node (ref "C87") (pin "2") (pinfunction "2_2") (pintype "passive"))
      (node (ref "C88") (pin "2") (pinfunction "2_2") (pintype "passive"))
      (node (ref "C89") (pin "2") (pinfunction "2_2") (pintype "passive"))
      (node (ref "C9") (pin "2") (pinfunction "2_2") (pintype "passive"))
      (node (ref "C90") (pin "2") (pinfunction "2_2") (pintype "passive"))
      (node (ref "C91") (pin "1") (pinfunction "1_1") (pintype "passive"))
      (node (ref "C92") (pin "2") (pinfunction "2_2") (pintype "passive"))
      (node (ref "C93") (pin "2") (pinfunction "2_2") (pintype "passive"))
      (node (ref "GND") (pin "TP") (pinfunction "TP_TP") (pintype "input"))
      (node (ref "GND75") (pin "TP") (pinfunction "TP_TP") (pintype "input"))
      (node (ref "GND77") (pin "TP") (pinfunction "TP_TP") (pintype "input"))
      (node (ref "R12") (pin "2") (pinfunction "2_2") (pintype "passive"))
      (node (ref "R15") (pin "2") (pinfunction "2_2") (pintype "passive"))
      (node (ref "R18") (pin "2") (pinfunction "2_2") (pintype "passive"))
      (node (ref "R22") (pin "1") (pinfunction "1_1") (pintype "passive"))
      (node (ref "R2X") (pin "2") (pinfunction "2_2") (pintype "passive"))
      (node (ref "R3") (pin "2") (pinfunction "2_2") (pintype "passive"))
      (node (ref "R6") (pin "2") (pinfunction "2_2") (pintype "passive"))
      (node (ref "R9") (pin "2") (pinfunction "2_2") (pintype "passive"))
      (node (ref "SENSOR") (pin "A21") (pinfunction "GND_A21") (pintype "power_in"))
      (node (ref "SENSOR") (pin "A25") (pinfunction "GND_A25") (pintype "power_in"))
      (node (ref "SENSOR") (pin "A28") (pinfunction "GND_A28") (pintype "power_in"))
      (node (ref "SENSOR") (pin "A29") (pinfunction "GND_A29") (pintype "power_in"))
      (node (ref "SENSOR") (pin "A9") (pinfunction "GND_A9") (pintype "power_in"))
      (node (ref "SENSOR") (pin "B22") (pinfunction "GND_B22") (pintype "power_in"))
      (node (ref "SENSOR") (pin "B26") (pinfunction "GND_B26") (pintype "power_in"))
      (node (ref "SENSOR") (pin "B27") (pinfunction "GND_B27") (pintype "power_in"))
      (node (ref "SENSOR") (pin "B28") (pinfunction "GND_B28") (pintype "power_in"))
      (node (ref "SENSOR") (pin "B5") (pinfunction "GND_B5") (pintype "power_in"))
      (node (ref "SENSOR") (pin "C15") (pinfunction "GND_C15") (pintype "power_in"))
      (node (ref "SENSOR") (pin "C16") (pinfunction "GND_C16") (pintype "power_in"))
      (node (ref "SENSOR") (pin "C28") (pinfunction "GND_C28") (pintype "power_in"))
      (node (ref "SENSOR") (pin "D2") (pinfunction "GND_D2") (pintype "power_in"))
      (node (ref "SENSOR") (pin "D25") (pinfunction "GND_D25") (pintype "power_in"))
      (node (ref "SENSOR") (pin "D27") (pinfunction "GND_D27") (pintype "power_in"))
      (node (ref "SENSOR") (pin "D29") (pinfunction "GND_D29") (pintype "power_in"))
      (node (ref "SENSOR") (pin "E15") (pinfunction "GND_E15") (pintype "power_in"))
      (node (ref "SENSOR") (pin "E16") (pinfunction "GND_E16") (pintype "power_in"))
      (node (ref "SENSOR") (pin "E25") (pinfunction "GND_E25") (pintype "power_in"))
      (node (ref "SENSOR") (pin "E27") (pinfunction "GND_E27") (pintype "power_in"))
      (node (ref "SENSOR") (pin "E3") (pinfunction "GND_E3") (pintype "power_in"))
      (node (ref "SENSOR") (pin "E4") (pinfunction "DIO2_E4") (pintype "output"))
      (node (ref "SENSOR") (pin "F27") (pinfunction "GND_F27") (pintype "power_in"))
      (node (ref "SENSOR") (pin "F4") (pinfunction "DIO1_F4") (pintype "output"))
      (node (ref "SENSOR") (pin "G3") (pinfunction "DIO4_G3") (pintype "output"))
      (node (ref "SENSOR") (pin "G5") (pinfunction "GND_G5") (pintype "power_in"))
      (node (ref "SENSOR") (pin "H1") (pinfunction "GND_H1") (pintype "power_in"))
      (node (ref "SENSOR") (pin "H21") (pinfunction "GND_H21") (pintype "power_in"))
      (node (ref "SENSOR") (pin "H25") (pinfunction "GND_H25") (pintype "power_in"))
      (node (ref "SENSOR") (pin "H27") (pinfunction "GND_H27") (pintype "power_in"))
      (node (ref "SENSOR") (pin "H4") (pinfunction "DIO3_H4") (pintype "output"))
      (node (ref "SENSOR") (pin "H6") (pinfunction "GND_H6") (pintype "power_in"))
      (node (ref "SENSOR") (pin "H9") (pinfunction "GND_H9") (pintype "power_in"))
      (node (ref "U1") (pin "6") (pinfunction "ANODE_6") (pintype "input"))
      (node (ref "U2") (pin "6") (pinfunction "ANODE_6") (pintype "input"))
      (node (ref "U3") (pin "2") (pinfunction "GND_2") (pintype "power_in"))
      (node (ref "U3") (pin "EP") (pinfunction "EP_EP") (pintype "power_in"))
      (node (ref "U4") (pin "16") (pinfunction "DIR2_16") (pintype "input"))
      (node (ref "U4") (pin "7") (pinfunction "~{OE}_7") (pintype "input"))
      (node (ref "U4") (pin "8") (pinfunction "GND_8") (pintype "passive"))
      (node (ref "U5") (pin "6") (pinfunction "DIR4_6") (pintype "input"))
      (node (ref "U5") (pin "7") (pinfunction "~{OE}_7") (pintype "input"))
      (node (ref "U5") (pin "8") (pinfunction "GND_8") (pintype "passive"))
      (node (ref "U6") (pin "16") (pinfunction "DIR2_16") (pintype "input"))
      (node (ref "U6") (pin "7") (pinfunction "~{OE}_7") (pintype "input"))
      (node (ref "U6") (pin "8") (pinfunction "GND_8") (pintype "passive"))
      (node (ref "U7") (pin "4") (pinfunction "GND_4") (pintype "power_in"))
      (node (ref "U7") (pin "5") (pinfunction "A2_5") (pintype "input"))
      (node (ref "U7") (pin "6") (pinfunction "A1_6") (pintype "input"))
      (node (ref "U7") (pin "7") (pinfunction "A0_7") (pintype "input"))
      (node (ref "UEP") (pin "1") (pinfunction "A0_1") (pintype "input"))
      (node (ref "UEP") (pin "2") (pinfunction "A1_2") (pintype "input"))
      (node (ref "UEP") (pin "3") (pinfunction "A2_3") (pintype "input"))
      (node (ref "UEP") (pin "4") (pinfunction "GND_4") (pintype "passive"))
      (node (ref "UEP") (pin "EP") (pinfunction "EP_EP") (pintype "passive"))
      (node (ref "UNE") (pin "4") (pinfunction "VSS_4") (pintype "power_in"))
      (node (ref "UNE") (pin "EP") (pinfunction "EP_EP") (pintype "passive"))
      (node (ref "UNN") (pin "4") (pinfunction "VSS_4") (pintype "power_in"))
      (node (ref "UNN") (pin "EP") (pinfunction "EP_EP") (pintype "passive"))
      (node (ref "UNW") (pin "4") (pinfunction "VSS_4") (pintype "power_in"))
      (node (ref "UNW") (pin "EP") (pinfunction "EP_EP") (pintype "passive"))
      (node (ref "USE") (pin "4") (pinfunction "VSS_4") (pintype "power_in"))
      (node (ref "USE") (pin "EP") (pinfunction "EP_EP") (pintype "passive"))
      (node (ref "USS") (pin "4") (pinfunction "VSS_4") (pintype "power_in"))
      (node (ref "USS") (pin "EP") (pinfunction "EP_EP") (pintype "passive"))
      (node (ref "USW") (pin "4") (pinfunction "VSS_4") (pintype "power_in"))
      (node (ref "USW") (pin "EP") (pinfunction "EP_EP") (pintype "passive"))
      (node (ref "X-NORTH") (pin "102") (pinfunction "102_102") (pintype "bidirectional"))
      (node (ref "X-NORTH") (pin "103") (pinfunction "103_103") (pintype "bidirectional"))
      (node (ref "X-NORTH") (pin "108") (pinfunction "108_108") (pintype "bidirectional"))
      (node (ref "X-NORTH") (pin "114") (pinfunction "114_114") (pintype "bidirectional"))
      (node (ref "X-NORTH") (pin "12") (pinfunction "12_12") (pintype "bidirectional"))
      (node (ref "X-NORTH") (pin "120") (pinfunction "120_120") (pintype "bidirectional"))
      (node (ref "X-NORTH") (pin "126") (pinfunction "126_126") (pintype "bidirectional"))
      (node (ref "X-NORTH") (pin "132") (pinfunction "132_132") (pintype "bidirectional"))
      (node (ref "X-NORTH") (pin "138") (pinfunction "138_138") (pintype "bidirectional"))
      (node (ref "X-NORTH") (pin "139") (pinfunction "139_139") (pintype "bidirectional"))
      (node (ref "X-NORTH") (pin "18") (pinfunction "18_18") (pintype "bidirectional"))
      (node (ref "X-NORTH") (pin "24") (pinfunction "24_24") (pintype "bidirectional"))
      (node (ref "X-NORTH") (pin "30") (pinfunction "30_30") (pintype "bidirectional"))
      (node (ref "X-NORTH") (pin "36") (pinfunction "36_36") (pintype "bidirectional"))
      (node (ref "X-NORTH") (pin "42") (pinfunction "42_42") (pintype "bidirectional"))
      (node (ref "X-NORTH") (pin "43") (pinfunction "43_43") (pintype "bidirectional"))
      (node (ref "X-NORTH") (pin "48") (pinfunction "48_48") (pintype "bidirectional"))
      (node (ref "X-NORTH") (pin "54") (pinfunction "54_54") (pintype "bidirectional"))
      (node (ref "X-NORTH") (pin "60") (pinfunction "60_60") (pintype "bidirectional"))
      (node (ref "X-NORTH") (pin "66") (pinfunction "66_66") (pintype "bidirectional"))
      (node (ref "X-NORTH") (pin "72") (pinfunction "72_72") (pintype "bidirectional"))
      (node (ref "X-NORTH") (pin "78") (pinfunction "78_78") (pintype "bidirectional"))
      (node (ref "X-NORTH") (pin "84") (pinfunction "84_84") (pintype "bidirectional"))
      (node (ref "X-NORTH") (pin "90") (pinfunction "90_90") (pintype "bidirectional"))
      (node (ref "X-NORTH") (pin "96") (pinfunction "96_96") (pintype "bidirectional"))
      (node (ref "X-SOUTH") (pin "102") (pinfunction "102_102") (pintype "bidirectional"))
      (node (ref "X-SOUTH") (pin "103") (pinfunction "103_103") (pintype "bidirectional"))
      (node (ref "X-SOUTH") (pin "108") (pinfunction "108_108") (pintype "bidirectional"))
      (node (ref "X-SOUTH") (pin "114") (pinfunction "114_114") (pintype "bidirectional"))
      (node (ref "X-SOUTH") (pin "12") (pinfunction "12_12") (pintype "bidirectional"))
      (node (ref "X-SOUTH") (pin "120") (pinfunction "120_120") (pintype "bidirectional"))
      (node (ref "X-SOUTH") (pin "126") (pinfunction "126_126") (pintype "bidirectional"))
      (node (ref "X-SOUTH") (pin "132") (pinfunction "132_132") (pintype "bidirectional"))
      (node (ref "X-SOUTH") (pin "138") (pinfunction "138_138") (pintype "bidirectional"))
      (node (ref "X-SOUTH") (pin "139") (pinfunction "139_139") (pintype "bidirectional"))
      (node (ref "X-SOUTH") (pin "18") (pinfunction "18_18") (pintype "bidirectional"))
      (node (ref "X-SOUTH") (pin "24") (pinfunction "24_24") (pintype "bidirectional"))
      (node (ref "X-SOUTH") (pin "30") (pinfunction "30_30") (pintype "bidirectional"))
      (node (ref "X-SOUTH") (pin "36") (pinfunction "36_36") (pintype "bidirectional"))
      (node (ref "X-SOUTH") (pin "42") (pinfunction "42_42") (pintype "bidirectional"))
      (node (ref "X-SOUTH") (pin "43") (pinfunction "43_43") (pintype "bidirectional"))
      (node (ref "X-SOUTH") (pin "48") (pinfunction "48_48") (pintype "bidirectional"))
      (node (ref "X-SOUTH") (pin "54") (pinfunction "54_54") (pintype "bidirectional"))
      (node (ref "X-SOUTH") (pin "60") (pinfunction "60_60") (pintype "bidirectional"))
      (node (ref "X-SOUTH") (pin "66") (pinfunction "66_66") (pintype "bidirectional"))
      (node (ref "X-SOUTH") (pin "72") (pinfunction "72_72") (pintype "bidirectional"))
      (node (ref "X-SOUTH") (pin "78") (pinfunction "78_78") (pintype "bidirectional"))
      (node (ref "X-SOUTH") (pin "84") (pinfunction "84_84") (pintype "bidirectional"))
      (node (ref "X-SOUTH") (pin "90") (pinfunction "90_90") (pintype "bidirectional"))
      (node (ref "X-SOUTH") (pin "96") (pinfunction "96_96") (pintype "bidirectional"))
    )
    (net (code "4") (name "N$42") (class "Default")
      (node (ref "SENSOR") (pin "A2") (pinfunction "TANA_A2") (pintype "output"))
    )
    (net (code "5") (name "N00_N") (class "Default")
      (node (ref "R25") (pin "2") (pinfunction "2_2") (pintype "passive"))
      (node (ref "SENSOR") (pin "E6") (pinfunction "LVDS_CLK_P_E6") (pintype "input"))
      (node (ref "X-NORTH") (pin "16") (pinfunction "16_16") (pintype "bidirectional"))
    )
    (net (code "6") (name "N00_P") (class "Default")
      (node (ref "R25") (pin "1") (pinfunction "1_1") (pintype "passive"))
      (node (ref "SENSOR") (pin "E5") (pinfunction "LVDS_CLK_N_E5") (pintype "input"))
      (node (ref "X-NORTH") (pin "14") (pinfunction "14_14") (pintype "bidirectional"))
    )
    (net (code "7") (name "N01_N") (class "Default")
      (node (ref "SENSOR") (pin "G7") (pinfunction "OUTCLK_P_G7") (pintype "output"))
      (node (ref "X-NORTH") (pin "17") (pinfunction "17_17") (pintype "bidirectional"))
    )
    (net (code "8") (name "N01_P") (class "Default")
      (node (ref "SENSOR") (pin "G6") (pinfunction "OUTCLK_N_G6") (pintype "output"))
      (node (ref "X-NORTH") (pin "15") (pinfunction "15_15") (pintype "bidirectional"))
    )
    (net (code "9") (name "N02_N") (class "Default")
      (node (ref "SENSOR") (pin "F7") (pinfunction "OUT33_P_F7") (pintype "output"))
      (node (ref "X-NORTH") (pin "22") (pinfunction "22_22") (pintype "bidirectional"))
    )
    (net (code "10") (name "N02_P") (class "Default")
      (node (ref "SENSOR") (pin "F6") (pinfunction "OUT33_N_F6") (pintype "output"))
      (node (ref "X-NORTH") (pin "20") (pinfunction "20_20") (pintype "bidirectional"))
    )
    (net (code "11") (name "N03_N") (class "Default")
      (node (ref "X-NORTH") (pin "23") (pinfunction "23_23") (pintype "bidirectional"))
    )
    (net (code "12") (name "N03_P") (class "Default")
      (node (ref "X-NORTH") (pin "21") (pinfunction "21_21") (pintype "bidirectional"))
    )
    (net (code "13") (name "N04_N") (class "Default")
      (node (ref "SENSOR") (pin "E8") (pinfunction "OUT35_P_E8") (pintype "output"))
      (node (ref "X-NORTH") (pin "28") (pinfunction "28_28") (pintype "bidirectional"))
    )
    (net (code "14") (name "N04_P") (class "Default")
      (node (ref "SENSOR") (pin "E7") (pinfunction "OUT35_N_E7") (pintype "output"))
      (node (ref "X-NORTH") (pin "26") (pinfunction "26_26") (pintype "bidirectional"))
    )
    (net (code "15") (name "N05_N") (class "Default")
      (node (ref "SENSOR") (pin "H8") (pinfunction "OUT34_P_H8") (pintype "output"))
      (node (ref "X-NORTH") (pin "29") (pinfunction "29_29") (pintype "bidirectional"))
    )
    (net (code "16") (name "N05_P") (class "Default")
      (node (ref "SENSOR") (pin "H7") (pinfunction "OUT34_N_H7") (pintype "output"))
      (node (ref "X-NORTH") (pin "27") (pinfunction "27_27") (pintype "bidirectional"))
    )
    (net (code "17") (name "N06_N") (class "Default")
      (node (ref "SENSOR") (pin "F9") (pinfunction "OUT37_P_F9") (pintype "output"))
      (node (ref "X-NORTH") (pin "34") (pinfunction "34_34") (pintype "bidirectional"))
    )
    (net (code "18") (name "N06_P") (class "Default")
      (node (ref "SENSOR") (pin "F8") (pinfunction "OUT37_N_F8") (pintype "output"))
      (node (ref "X-NORTH") (pin "32") (pinfunction "32_32") (pintype "bidirectional"))
    )
    (net (code "19") (name "N07_N") (class "Default")
      (node (ref "SENSOR") (pin "G9") (pinfunction "OUT36_P_G9") (pintype "output"))
      (node (ref "X-NORTH") (pin "35") (pinfunction "35_35") (pintype "bidirectional"))
    )
    (net (code "20") (name "N07_P") (class "Default")
      (node (ref "SENSOR") (pin "G8") (pinfunction "OUT36_N_G8") (pintype "output"))
      (node (ref "X-NORTH") (pin "33") (pinfunction "33_33") (pintype "bidirectional"))
    )
    (net (code "21") (name "N08_N") (class "Default")
      (node (ref "SENSOR") (pin "E10") (pinfunction "OUT38_P_E10") (pintype "output"))
      (node (ref "X-NORTH") (pin "40") (pinfunction "40_40") (pintype "bidirectional"))
    )
    (net (code "22") (name "N08_P") (class "Default")
      (node (ref "SENSOR") (pin "E9") (pinfunction "OUT38_N_E9") (pintype "output"))
      (node (ref "X-NORTH") (pin "38") (pinfunction "38_38") (pintype "bidirectional"))
    )
    (net (code "23") (name "N09_N") (class "Default")
      (node (ref "SENSOR") (pin "G11") (pinfunction "OUT39_P_G11") (pintype "output"))
      (node (ref "X-NORTH") (pin "41") (pinfunction "41_41") (pintype "bidirectional"))
    )
    (net (code "24") (name "N09_P") (class "Default")
      (node (ref "SENSOR") (pin "G10") (pinfunction "OUT39_N_G10") (pintype "output"))
      (node (ref "X-NORTH") (pin "39") (pinfunction "39_39") (pintype "bidirectional"))
    )
    (net (code "25") (name "N10_N") (class "Default")
      (node (ref "SENSOR") (pin "F11") (pinfunction "OUT40_P_F11") (pintype "output"))
      (node (ref "X-NORTH") (pin "46") (pinfunction "46_46") (pintype "bidirectional"))
    )
    (net (code "26") (name "N10_P") (class "Default")
      (node (ref "SENSOR") (pin "F10") (pinfunction "OUT40_N_F10") (pintype "output"))
      (node (ref "X-NORTH") (pin "44") (pinfunction "44_44") (pintype "bidirectional"))
    )
    (net (code "27") (name "N11_N") (class "Default")
      (node (ref "SENSOR") (pin "H12") (pinfunction "OUT41_P_H12") (pintype "output"))
      (node (ref "X-NORTH") (pin "47") (pinfunction "47_47") (pintype "bidirectional"))
    )
    (net (code "28") (name "N11_P") (class "Default")
      (node (ref "SENSOR") (pin "H11") (pinfunction "OUT41_N_H11") (pintype "output"))
      (node (ref "X-NORTH") (pin "45") (pinfunction "45_45") (pintype "bidirectional"))
    )
    (net (code "29") (name "N12_N") (class "Default")
      (node (ref "SENSOR") (pin "E12") (pinfunction "OUT42_P_E12") (pintype "output"))
      (node (ref "X-NORTH") (pin "52") (pinfunction "52_52") (pintype "bidirectional"))
    )
    (net (code "30") (name "N12_P") (class "Default")
      (node (ref "SENSOR") (pin "E11") (pinfunction "OUT42_N_E11") (pintype "output"))
      (node (ref "X-NORTH") (pin "50") (pinfunction "50_50") (pintype "bidirectional"))
    )
    (net (code "31") (name "N13_N") (class "Default")
      (node (ref "SENSOR") (pin "G13") (pinfunction "OUT43_P_G13") (pintype "output"))
      (node (ref "X-NORTH") (pin "53") (pinfunction "53_53") (pintype "bidirectional"))
    )
    (net (code "32") (name "N13_P") (class "Default")
      (node (ref "SENSOR") (pin "G12") (pinfunction "OUT43_N_G12") (pintype "output"))
      (node (ref "X-NORTH") (pin "51") (pinfunction "51_51") (pintype "bidirectional"))
    )
    (net (code "33") (name "N14_N") (class "Default")
      (node (ref "SENSOR") (pin "F13") (pinfunction "OUT44_P_F13") (pintype "output"))
      (node (ref "X-NORTH") (pin "58") (pinfunction "58_58") (pintype "bidirectional"))
    )
    (net (code "34") (name "N14_P") (class "Default")
      (node (ref "SENSOR") (pin "F12") (pinfunction "OUT44_N_F12") (pintype "output"))
      (node (ref "X-NORTH") (pin "56") (pinfunction "56_56") (pintype "bidirectional"))
    )
    (net (code "35") (name "N15_N") (class "Default")
      (node (ref "SENSOR") (pin "H14") (pinfunction "OUT45_P_H14") (pintype "output"))
      (node (ref "X-NORTH") (pin "59") (pinfunction "59_59") (pintype "bidirectional"))
    )
    (net (code "36") (name "N15_P") (class "Default")
      (node (ref "SENSOR") (pin "H13") (pinfunction "OUT45_N_H13") (pintype "output"))
      (node (ref "X-NORTH") (pin "57") (pinfunction "57_57") (pintype "bidirectional"))
    )
    (net (code "37") (name "N16_N") (class "Default")
      (node (ref "SENSOR") (pin "E14") (pinfunction "OUT46_P_E14") (pintype "output"))
      (node (ref "X-NORTH") (pin "64") (pinfunction "64_64") (pintype "bidirectional"))
    )
    (net (code "38") (name "N16_P") (class "Default")
      (node (ref "SENSOR") (pin "E13") (pinfunction "OUT46_N_E13") (pintype "output"))
      (node (ref "X-NORTH") (pin "62") (pinfunction "62_62") (pintype "bidirectional"))
    )
    (net (code "39") (name "N17_N") (class "Default")
      (node (ref "SENSOR") (pin "G15") (pinfunction "OUT47_P_G15") (pintype "output"))
      (node (ref "X-NORTH") (pin "65") (pinfunction "65_65") (pintype "bidirectional"))
    )
    (net (code "40") (name "N17_P") (class "Default")
      (node (ref "SENSOR") (pin "G14") (pinfunction "OUT47_N_G14") (pintype "output"))
      (node (ref "X-NORTH") (pin "63") (pinfunction "63_63") (pintype "bidirectional"))
    )
    (net (code "41") (name "N18_N") (class "Default")
      (node (ref "SENSOR") (pin "F15") (pinfunction "OUT48_P_F15") (pintype "output"))
      (node (ref "X-NORTH") (pin "70") (pinfunction "70_70") (pintype "bidirectional"))
    )
    (net (code "42") (name "N18_P") (class "Default")
      (node (ref "SENSOR") (pin "F14") (pinfunction "OUT48_N_F14") (pintype "output"))
      (node (ref "X-NORTH") (pin "68") (pinfunction "68_68") (pintype "bidirectional"))
    )
    (net (code "43") (name "N19_N") (class "Default")
      (node (ref "SENSOR") (pin "G17") (pinfunction "OUT50_P_G17") (pintype "output"))
      (node (ref "X-NORTH") (pin "71") (pinfunction "71_71") (pintype "bidirectional"))
    )
    (net (code "44") (name "N19_P") (class "Default")
      (node (ref "SENSOR") (pin "G16") (pinfunction "OUT50_N_G16") (pintype "output"))
      (node (ref "X-NORTH") (pin "69") (pinfunction "69_69") (pintype "bidirectional"))
    )
    (net (code "45") (name "N20_N") (class "Default")
      (node (ref "SENSOR") (pin "F17") (pinfunction "OUT49_P_F17") (pintype "output"))
      (node (ref "X-NORTH") (pin "76") (pinfunction "76_76") (pintype "bidirectional"))
    )
    (net (code "46") (name "N20_P") (class "Default")
      (node (ref "SENSOR") (pin "F16") (pinfunction "OUT49_N_F16") (pintype "output"))
      (node (ref "X-NORTH") (pin "74") (pinfunction "74_74") (pintype "bidirectional"))
    )
    (net (code "47") (name "N21_N") (class "Default")
      (node (ref "SENSOR") (pin "H18") (pinfunction "OUT52_P_H18") (pintype "output"))
      (node (ref "X-NORTH") (pin "77") (pinfunction "77_77") (pintype "bidirectional"))
    )
    (net (code "48") (name "N21_P") (class "Default")
      (node (ref "SENSOR") (pin "H17") (pinfunction "OUT52_N_H17") (pintype "output"))
      (node (ref "X-NORTH") (pin "75") (pinfunction "75_75") (pintype "bidirectional"))
    )
    (net (code "49") (name "N22_N") (class "Default")
      (node (ref "SENSOR") (pin "E18") (pinfunction "OUT51_P_E18") (pintype "output"))
      (node (ref "X-NORTH") (pin "82") (pinfunction "82_82") (pintype "bidirectional"))
    )
    (net (code "50") (name "N22_P") (class "Default")
      (node (ref "SENSOR") (pin "E17") (pinfunction "OUT51_N_E17") (pintype "output"))
      (node (ref "X-NORTH") (pin "80") (pinfunction "80_80") (pintype "bidirectional"))
    )
    (net (code "51") (name "N23_N") (class "Default")
      (node (ref "SENSOR") (pin "G19") (pinfunction "OUT54_P_G19") (pintype "output"))
      (node (ref "X-NORTH") (pin "83") (pinfunction "83_83") (pintype "bidirectional"))
    )
    (net (code "52") (name "N23_P") (class "Default")
      (node (ref "SENSOR") (pin "G18") (pinfunction "OUT54_N_G18") (pintype "output"))
      (node (ref "X-NORTH") (pin "81") (pinfunction "81_81") (pintype "bidirectional"))
    )
    (net (code "53") (name "N24_N") (class "Default")
      (node (ref "SENSOR") (pin "F19") (pinfunction "OUT53_P_F19") (pintype "output"))
      (node (ref "X-NORTH") (pin "88") (pinfunction "88_88") (pintype "bidirectional"))
    )
    (net (code "54") (name "N24_P") (class "Default")
      (node (ref "SENSOR") (pin "F18") (pinfunction "OUT53_N_F18") (pintype "output"))
      (node (ref "X-NORTH") (pin "86") (pinfunction "86_86") (pintype "bidirectional"))
    )
    (net (code "55") (name "N25_N") (class "Default")
      (node (ref "SENSOR") (pin "H20") (pinfunction "OUT56_P_H20") (pintype "output"))
      (node (ref "X-NORTH") (pin "89") (pinfunction "89_89") (pintype "bidirectional"))
    )
    (net (code "56") (name "N25_P") (class "Default")
      (node (ref "SENSOR") (pin "H19") (pinfunction "OUT56_N_H19") (pintype "output"))
      (node (ref "X-NORTH") (pin "87") (pinfunction "87_87") (pintype "bidirectional"))
    )
    (net (code "57") (name "N26_N") (class "Default")
      (node (ref "SENSOR") (pin "E20") (pinfunction "OUT55_P_E20") (pintype "output"))
      (node (ref "X-NORTH") (pin "94") (pinfunction "94_94") (pintype "bidirectional"))
    )
    (net (code "58") (name "N26_P") (class "Default")
      (node (ref "SENSOR") (pin "E19") (pinfunction "OUT55_N_E19") (pintype "output"))
      (node (ref "X-NORTH") (pin "92") (pinfunction "92_92") (pintype "bidirectional"))
    )
    (net (code "59") (name "N27_N") (class "Default")
      (node (ref "SENSOR") (pin "G21") (pinfunction "OUT58_P_G21") (pintype "output"))
      (node (ref "X-NORTH") (pin "95") (pinfunction "95_95") (pintype "bidirectional"))
    )
    (net (code "60") (name "N27_P") (class "Default")
      (node (ref "SENSOR") (pin "G20") (pinfunction "OUT58_N_G20") (pintype "output"))
      (node (ref "X-NORTH") (pin "93") (pinfunction "93_93") (pintype "bidirectional"))
    )
    (net (code "61") (name "N28_N") (class "Default")
      (node (ref "SENSOR") (pin "F21") (pinfunction "OUT57_P_F21") (pintype "output"))
      (node (ref "X-NORTH") (pin "100") (pinfunction "100_100") (pintype "bidirectional"))
    )
    (net (code "62") (name "N28_P") (class "Default")
      (node (ref "SENSOR") (pin "F20") (pinfunction "OUT57_N_F20") (pintype "output"))
      (node (ref "X-NORTH") (pin "98") (pinfunction "98_98") (pintype "bidirectional"))
    )
    (net (code "63") (name "N29_N") (class "Default")
      (node (ref "SENSOR") (pin "G23") (pinfunction "OUT61_P_G23") (pintype "output"))
      (node (ref "X-NORTH") (pin "101") (pinfunction "101_101") (pintype "bidirectional"))
    )
    (net (code "64") (name "N29_P") (class "Default")
      (node (ref "SENSOR") (pin "G22") (pinfunction "OUT61_N_G22") (pintype "output"))
      (node (ref "X-NORTH") (pin "99") (pinfunction "99_99") (pintype "bidirectional"))
    )
    (net (code "65") (name "N30_N") (class "Default")
      (node (ref "SENSOR") (pin "E22") (pinfunction "OUT59_P_E22") (pintype "output"))
      (node (ref "X-NORTH") (pin "106") (pinfunction "106_106") (pintype "bidirectional"))
    )
    (net (code "66") (name "N30_P") (class "Default")
      (node (ref "SENSOR") (pin "E21") (pinfunction "OUT59_N_E21") (pintype "output"))
      (node (ref "X-NORTH") (pin "104") (pinfunction "104_104") (pintype "bidirectional"))
    )
    (net (code "67") (name "N31_N") (class "Default")
      (node (ref "SENSOR") (pin "H24") (pinfunction "OUT63_P_H24") (pintype "output"))
      (node (ref "X-NORTH") (pin "107") (pinfunction "107_107") (pintype "bidirectional"))
    )
    (net (code "68") (name "N31_P") (class "Default")
      (node (ref "SENSOR") (pin "H23") (pinfunction "OUT63_N_H23") (pintype "output"))
      (node (ref "X-NORTH") (pin "105") (pinfunction "105_105") (pintype "bidirectional"))
    )
    (net (code "69") (name "N32_N") (class "Default")
      (node (ref "SENSOR") (pin "F23") (pinfunction "OUT60_P_F23") (pintype "output"))
      (node (ref "X-NORTH") (pin "112") (pinfunction "112_112") (pintype "bidirectional"))
    )
    (net (code "70") (name "N32_P") (class "Default")
      (node (ref "SENSOR") (pin "F22") (pinfunction "OUT60_N_F22") (pintype "output"))
      (node (ref "X-NORTH") (pin "110") (pinfunction "110_110") (pintype "bidirectional"))
    )
    (net (code "71") (name "N33_N") (class "Default")
      (node (ref "SENSOR") (pin "G25") (pinfunction "OUT64_P_G25") (pintype "output"))
      (node (ref "X-NORTH") (pin "113") (pinfunction "113_113") (pintype "bidirectional"))
    )
    (net (code "72") (name "N33_P") (class "Default")
      (node (ref "SENSOR") (pin "G24") (pinfunction "OUT64_N_G24") (pintype "output"))
      (node (ref "X-NORTH") (pin "111") (pinfunction "111_111") (pintype "bidirectional"))
    )
    (net (code "73") (name "N34_N") (class "Default")
      (node (ref "SENSOR") (pin "E24") (pinfunction "OUT62_P_E24") (pintype "output"))
      (node (ref "X-NORTH") (pin "118") (pinfunction "118_118") (pintype "bidirectional"))
    )
    (net (code "74") (name "N34_P") (class "Default")
      (node (ref "SENSOR") (pin "E23") (pinfunction "OUT62_N_E23") (pintype "output"))
      (node (ref "X-NORTH") (pin "116") (pinfunction "116_116") (pintype "bidirectional"))
    )
    (net (code "75") (name "N35_N") (class "Default")
      (node (ref "U6") (pin "4") (pinfunction "A4_4") (pintype "bidirectional"))
      (node (ref "X-NORTH") (pin "119") (pinfunction "119_119") (pintype "bidirectional"))
    )
    (net (code "76") (name "N35_P") (class "Default")
      (node (ref "U6") (pin "3") (pinfunction "A3_3") (pintype "bidirectional"))
      (node (ref "X-NORTH") (pin "117") (pinfunction "117_117") (pintype "bidirectional"))
    )
    (net (code "77") (name "N36_N") (class "Default")
      (node (ref "X-NORTH") (pin "124") (pinfunction "124_124") (pintype "bidirectional"))
    )
    (net (code "78") (name "N36_P") (class "Default")
      (node (ref "X-NORTH") (pin "122") (pinfunction "122_122") (pintype "bidirectional"))
    )
    (net (code "79") (name "N37_N") (class "Default")
      (node (ref "U5") (pin "3") (pinfunction "A3_3") (pintype "bidirectional"))
      (node (ref "X-NORTH") (pin "125") (pinfunction "125_125") (pintype "bidirectional"))
    )
    (net (code "80") (name "N37_P") (class "Default")
      (node (ref "U5") (pin "4") (pinfunction "A4_4") (pintype "bidirectional"))
      (node (ref "X-NORTH") (pin "123") (pinfunction "123_123") (pintype "bidirectional"))
    )
    (net (code "81") (name "N38_N") (class "Default")
      (node (ref "U6") (pin "2") (pinfunction "A2_2") (pintype "bidirectional"))
      (node (ref "X-NORTH") (pin "130") (pinfunction "130_130") (pintype "bidirectional"))
    )
    (net (code "82") (name "N38_P") (class "Default")
      (node (ref "U6") (pin "1") (pinfunction "A1_1") (pintype "bidirectional"))
      (node (ref "X-NORTH") (pin "128") (pinfunction "128_128") (pintype "bidirectional"))
    )
    (net (code "83") (name "N39_N") (class "Default")
      (node (ref "U5") (pin "1") (pinfunction "A1_1") (pintype "bidirectional"))
      (node (ref "X-NORTH") (pin "131") (pinfunction "131_131") (pintype "bidirectional"))
    )
    (net (code "84") (name "N39_P") (class "Default")
      (node (ref "U5") (pin "2") (pinfunction "A2_2") (pintype "bidirectional"))
      (node (ref "X-NORTH") (pin "129") (pinfunction "129_129") (pintype "bidirectional"))
    )
    (net (code "85") (name "N_CHK_EN") (class "Default")
      (node (ref "X-NORTH") (pin "8") (pinfunction "8_8") (pintype "bidirectional"))
    )
    (net (code "86") (name "N_CHK_V") (class "Default")
      (node (ref "C2") (pin "1") (pinfunction "1_1") (pintype "passive"))
      (node (ref "C3") (pin "1") (pinfunction "1_1") (pintype "passive"))
      (node (ref "C4") (pin "1") (pinfunction "1_1") (pintype "passive"))
      (node (ref "R19") (pin "1") (pinfunction "1_1") (pintype "passive"))
      (node (ref "TP1") (pin "TP") (pinfunction "TP_TP") (pintype "input"))
      (node (ref "UNE") (pin "8") (pinfunction "VDD_8") (pintype "power_in"))
      (node (ref "UNN") (pin "8") (pinfunction "VDD_8") (pintype "power_in"))
      (node (ref "UNW") (pin "8") (pinfunction "VDD_8") (pintype "power_in"))
      (node (ref "X-NORTH") (pin "10") (pinfunction "10_10") (pintype "bidirectional"))
    )
    (net (code "87") (name "N_I2C_EN") (class "Default")
      (node (ref "X-NORTH") (pin "137") (pinfunction "137_137") (pintype "bidirectional"))
    )
    (net (code "88") (name "N_I2C_V") (class "Default")
      (node (ref "C1") (pin "1") (pinfunction "1_1") (pintype "passive"))
      (node (ref "R1X") (pin "1") (pinfunction "1_1") (pintype "passive"))
      (node (ref "UEP") (pin "8") (pinfunction "VCC_8") (pintype "power_in"))
      (node (ref "X-NORTH") (pin "135") (pinfunction "135_135") (pintype "bidirectional"))
    )
    (net (code "89") (name "N_REF") (class "Default")
      (node (ref "R19") (pin "2") (pinfunction "2_2") (pintype "passive"))
      (node (ref "TP2") (pin "TP") (pinfunction "TP_TP") (pintype "input"))
      (node (ref "U1") (pin "1") (pinfunction "CATHODE_1") (pintype "output"))
      (node (ref "U1") (pin "3") (pinfunction "REF_3") (pintype "input"))
      (node (ref "UNE") (pin "2") (pinfunction "VINA-_2") (pintype "input"))
      (node (ref "UNE") (pin "5") (pinfunction "VINB+_5") (pintype "input"))
      (node (ref "UNN") (pin "2") (pinfunction "VINA-_2") (pintype "input"))
      (node (ref "UNN") (pin "5") (pinfunction "VINB+_5") (pintype "input"))
      (node (ref "UNW") (pin "2") (pinfunction "VINA-_2") (pintype "input"))
      (node (ref "UNW") (pin "5") (pinfunction "VINB+_5") (pintype "input"))
    )
    (net (code "90") (name "N_SCK") (class "Default")
      (node (ref "U4") (pin "4") (pinfunction "A4_4") (pintype "bidirectional"))
      (node (ref "X-NORTH") (pin "144") (pinfunction "144_144") (pintype "bidirectional"))
    )
    (net (code "91") (name "N_SCL") (class "Default")
      (node (ref "UEP") (pin "6") (pinfunction "SCL_6") (pintype "input"))
      (node (ref "X-NORTH") (pin "143") (pinfunction "143_143") (pintype "bidirectional"))
    )
    (net (code "92") (name "N_SDA") (class "Default")
      (node (ref "UEP") (pin "5") (pinfunction "SDA_5") (pintype "bidirectional"))
      (node (ref "X-NORTH") (pin "141") (pinfunction "141_141") (pintype "bidirectional"))
    )
    (net (code "93") (name "N_SDI") (class "Default")
      (node (ref "U4") (pin "2") (pinfunction "A2_2") (pintype "bidirectional"))
      (node (ref "X-NORTH") (pin "140") (pinfunction "140_140") (pintype "bidirectional"))
    )
    (net (code "94") (name "N_SDO") (class "Default")
      (node (ref "U4") (pin "3") (pinfunction "A3_3") (pintype "bidirectional"))
      (node (ref "X-NORTH") (pin "142") (pinfunction "142_142") (pintype "bidirectional"))
    )
    (net (code "95") (name "N_SPI_EN") (class "Default")
      (node (ref "U4") (pin "1") (pinfunction "A1_1") (pintype "bidirectional"))
      (node (ref "X-NORTH") (pin "136") (pinfunction "136_136") (pintype "bidirectional"))
    )
    (net (code "96") (name "N_SPI_V") (class "Default")
      (node (ref "C59") (pin "1") (pinfunction "1_1") (pintype "passive"))
      (node (ref "U4") (pin "14") (pinfunction "VCCA_14") (pintype "power_in"))
      (node (ref "U4") (pin "15") (pinfunction "DIR1_15") (pintype "input"))
      (node (ref "U4") (pin "5") (pinfunction "DIR3_5") (pintype "input"))
      (node (ref "U4") (pin "6") (pinfunction "DIR4_6") (pintype "input"))
      (node (ref "X-NORTH") (pin "134") (pinfunction "134_134") (pintype "bidirectional"))
    )
    (net (code "97") (name "N_VE") (class "Default")
      (node (ref "C22") (pin "1") (pinfunction "1_1") (pintype "passive"))
      (node (ref "C23") (pin "1") (pinfunction "1_1") (pintype "passive"))
      (node (ref "C24") (pin "1") (pinfunction "1_1") (pintype "passive"))
      (node (ref "C25") (pin "1") (pinfunction "1_1") (pintype "passive"))
      (node (ref "C26") (pin "1") (pinfunction "1_1") (pintype "passive"))
      (node (ref "C27") (pin "1") (pinfunction "1_1") (pintype "passive"))
      (node (ref "C28") (pin "1") (pinfunction "1_1") (pintype "passive"))
      (node (ref "C50") (pin "1") (pinfunction "1_1") (pintype "passive"))
      (node (ref "C51") (pin "1") (pinfunction "1_1") (pintype "passive"))
      (node (ref "C52") (pin "1") (pinfunction "1_1") (pintype "passive"))
      (node (ref "C53") (pin "1") (pinfunction "1_1") (pintype "passive"))
      (node (ref "C54") (pin "1") (pinfunction "1_1") (pintype "passive"))
      (node (ref "C55") (pin "1") (pinfunction "1_1") (pintype "passive"))
      (node (ref "C56") (pin "1") (pinfunction "1_1") (pintype "passive"))
      (node (ref "C67") (pin "1") (pinfunction "1_1") (pintype "passive"))
      (node (ref "C69") (pin "1") (pinfunction "1_1") (pintype "passive"))
      (node (ref "C75") (pin "1") (pinfunction "1_1") (pintype "passive"))
      (node (ref "C76") (pin "1") (pinfunction "1_1") (pintype "passive"))
      (node (ref "C77") (pin "1") (pinfunction "1_1") (pintype "passive"))
      (node (ref "C84") (pin "1") (pinfunction "1_1") (pintype "passive"))
      (node (ref "C85") (pin "1") (pinfunction "1_1") (pintype "passive"))
      (node (ref "C86") (pin "1") (pinfunction "1_1") (pintype "passive"))
      (node (ref "C93") (pin "1") (pinfunction "1_1") (pintype "passive"))
      (node (ref "SENSOR") (pin "C26") (pinfunction "VDD33_C26") (pintype "power_in"))
      (node (ref "SENSOR") (pin "C27") (pinfunction "VDD33_C27") (pintype "power_in"))
      (node (ref "SENSOR") (pin "D26") (pinfunction "VDD33_D26") (pintype "power_in"))
      (node (ref "SENSOR") (pin "D3") (pinfunction "VDD33_D3") (pintype "power_in"))
      (node (ref "SENSOR") (pin "E26") (pinfunction "VDD33_E26") (pintype "power_in"))
      (node (ref "SENSOR") (pin "F26") (pinfunction "VDD33_F26") (pintype "power_in"))
      (node (ref "SENSOR") (pin "F5") (pinfunction "VDD33_F5") (pintype "power_in"))
      (node (ref "TP7") (pin "TP") (pinfunction "TP_TP") (pintype "input"))
      (node (ref "U4") (pin "13") (pinfunction "VCCB_13") (pintype "power_in"))
      (node (ref "U5") (pin "13") (pinfunction "VCCB_13") (pintype "power_in"))
      (node (ref "U6") (pin "13") (pinfunction "VCCB_13") (pintype "power_in"))
      (node (ref "X-NORTH") (pin "109") (pinfunction "109_109") (pintype "bidirectional"))
      (node (ref "X-NORTH") (pin "115") (pinfunction "115_115") (pintype "bidirectional"))
      (node (ref "X-NORTH") (pin "121") (pinfunction "121_121") (pintype "bidirectional"))
      (node (ref "X-NORTH") (pin "127") (pinfunction "127_127") (pintype "bidirectional"))
      (node (ref "X-NORTH") (pin "133") (pinfunction "133_133") (pintype "bidirectional"))
    )
    (net (code "98") (name "N_VE_CV") (class "Default")
      (node (ref "C10") (pin "1") (pinfunction "1_1") (pintype "passive"))
      (node (ref "R7") (pin "1") (pinfunction "1_1") (pintype "passive"))
      (node (ref "X-NORTH") (pin "6") (pinfunction "6_6") (pintype "bidirectional"))
    )
    (net (code "99") (name "N_VE_OV") (class "Default")
      (node (ref "UNE") (pin "7") (pinfunction "OUTB_7") (pintype "output"))
      (node (ref "X-NORTH") (pin "5") (pinfunction "5_5") (pintype "bidirectional"))
    )
    (net (code "100") (name "N_VE_UV") (class "Default")
      (node (ref "UNE") (pin "1") (pinfunction "OUTA_1") (pintype "output"))
      (node (ref "X-NORTH") (pin "11") (pinfunction "11_11") (pintype "bidirectional"))
    )
    (net (code "101") (name "N_VN") (class "Default")
      (node (ref "C31") (pin "1") (pinfunction "1_1") (pintype "passive"))
      (node (ref "C32") (pin "1") (pinfunction "1_1") (pintype "passive"))
      (node (ref "C33") (pin "1") (pinfunction "1_1") (pintype "passive"))
      (node (ref "C34") (pin "1") (pinfunction "1_1") (pintype "passive"))
      (node (ref "C35") (pin "1") (pinfunction "1_1") (pintype "passive"))
      (node (ref "C36") (pin "1") (pinfunction "1_1") (pintype "passive"))
      (node (ref "C37") (pin "1") (pinfunction "1_1") (pintype "passive"))
      (node (ref "C38") (pin "1") (pinfunction "1_1") (pintype "passive"))
      (node (ref "C39") (pin "1") (pinfunction "1_1") (pintype "passive"))
      (node (ref "C40") (pin "1") (pinfunction "1_1") (pintype "passive"))
      (node (ref "C41") (pin "1") (pinfunction "1_1") (pintype "passive"))
      (node (ref "C42") (pin "1") (pinfunction "1_1") (pintype "passive"))
      (node (ref "C43") (pin "1") (pinfunction "1_1") (pintype "passive"))
      (node (ref "C44") (pin "1") (pinfunction "1_1") (pintype "passive"))
      (node (ref "C68") (pin "1") (pinfunction "1_1") (pintype "passive"))
      (node (ref "C70") (pin "1") (pinfunction "1_1") (pintype "passive"))
      (node (ref "C78") (pin "1") (pinfunction "1_1") (pintype "passive"))
      (node (ref "C79") (pin "1") (pinfunction "1_1") (pintype "passive"))
      (node (ref "C80") (pin "1") (pinfunction "1_1") (pintype "passive"))
      (node (ref "C87") (pin "1") (pinfunction "1_1") (pintype "passive"))
      (node (ref "C88") (pin "1") (pinfunction "1_1") (pintype "passive"))
      (node (ref "C89") (pin "1") (pinfunction "1_1") (pintype "passive"))
      (node (ref "SENSOR") (pin "A10") (pinfunction "VDD18_A10") (pintype "power_in"))
      (node (ref "SENSOR") (pin "A15") (pinfunction "VDD18_A15") (pintype "power_in"))
      (node (ref "SENSOR") (pin "A16") (pinfunction "VDD18_A16") (pintype "power_in"))
      (node (ref "SENSOR") (pin "A22") (pinfunction "VDD18_A22") (pintype "power_in"))
      (node (ref "SENSOR") (pin "A26") (pinfunction "VDD18_A26") (pintype "power_in"))
      (node (ref "SENSOR") (pin "A27") (pinfunction "VDD18_A27") (pintype "power_in"))
      (node (ref "SENSOR") (pin "B4") (pinfunction "VDD18_B4") (pintype "power_in"))
      (node (ref "SENSOR") (pin "E1") (pinfunction "VDD18_PLL_E1") (pintype "power_in"))
      (node (ref "SENSOR") (pin "H10") (pinfunction "VDD18_H10") (pintype "power_in"))
      (node (ref "SENSOR") (pin "H15") (pinfunction "VDD18_H15") (pintype "power_in"))
      (node (ref "SENSOR") (pin "H16") (pinfunction "VDD18_H16") (pintype "power_in"))
      (node (ref "SENSOR") (pin "H22") (pinfunction "VDD18_H22") (pintype "power_in"))
      (node (ref "SENSOR") (pin "H26") (pinfunction "VDD18_H26") (pintype "power_in"))
      (node (ref "SENSOR") (pin "H5") (pinfunction "VDD18_H5") (pintype "power_in"))
      (node (ref "TP5") (pin "TP") (pinfunction "TP_TP") (pintype "input"))
      (node (ref "U5") (pin "14") (pinfunction "VCCA_14") (pintype "power_in"))
      (node (ref "U5") (pin "15") (pinfunction "DIR1_15") (pintype "input"))
      (node (ref "U5") (pin "16") (pinfunction "DIR2_16") (pintype "input"))
      (node (ref "U5") (pin "5") (pinfunction "DIR3_5") (pintype "input"))
      (node (ref "U6") (pin "14") (pinfunction "VCCA_14") (pintype "power_in"))
      (node (ref "U6") (pin "15") (pinfunction "DIR1_15") (pintype "input"))
      (node (ref "U6") (pin "5") (pinfunction "DIR3_5") (pintype "input"))
      (node (ref "U6") (pin "6") (pinfunction "DIR4_6") (pintype "input"))
      (node (ref "X-NORTH") (pin "49") (pinfunction "49_49") (pintype "bidirectional"))
      (node (ref "X-NORTH") (pin "55") (pinfunction "55_55") (pintype "bidirectional"))
      (node (ref "X-NORTH") (pin "61") (pinfunction "61_61") (pintype "bidirectional"))
      (node (ref "X-NORTH") (pin "67") (pinfunction "67_67") (pintype "bidirectional"))
      (node (ref "X-NORTH") (pin "73") (pinfunction "73_73") (pintype "bidirectional"))
      (node (ref "X-NORTH") (pin "79") (pinfunction "79_79") (pintype "bidirectional"))
      (node (ref "X-NORTH") (pin "85") (pinfunction "85_85") (pintype "bidirectional"))
      (node (ref "X-NORTH") (pin "91") (pinfunction "91_91") (pintype "bidirectional"))
      (node (ref "X-NORTH") (pin "97") (pinfunction "97_97") (pintype "bidirectional"))
    )
    (net (code "102") (name "N_VN_CV") (class "Default")
      (node (ref "C9") (pin "1") (pinfunction "1_1") (pintype "passive"))
      (node (ref "R4") (pin "1") (pinfunction "1_1") (pintype "passive"))
      (node (ref "X-NORTH") (pin "4") (pinfunction "4_4") (pintype "bidirectional"))
    )
    (net (code "103") (name "N_VN_OV") (class "Default")
      (node (ref "UNN") (pin "7") (pinfunction "OUTB_7") (pintype "output"))
      (node (ref "X-NORTH") (pin "3") (pinfunction "3_3") (pintype "bidirectional"))
    )
    (net (code "104") (name "N_VN_UV") (class "Default")
      (node (ref "UNN") (pin "1") (pinfunction "OUTA_1") (pintype "output"))
      (node (ref "X-NORTH") (pin "9") (pinfunction "9_9") (pintype "bidirectional"))
    )
    (net (code "105") (name "N_VW") (class "Default")
      (node (ref "C57") (pin "1") (pinfunction "1_1") (pintype "passive"))
      (node (ref "C58") (pin "1") (pinfunction "1_1") (pintype "passive"))
      (node (ref "C92") (pin "1") (pinfunction "1_1") (pintype "passive"))
      (node (ref "SENSOR") (pin "E2") (pinfunction "VDD_RES_E2") (pintype "power_in"))
      (node (ref "SENSOR") (pin "G4") (pinfunction "VDD_RES_G4") (pintype "power_in"))
      (node (ref "TP8") (pin "TP") (pinfunction "TP_TP") (pintype "input"))
      (node (ref "X-NORTH") (pin "13") (pinfunction "13_13") (pintype "bidirectional"))
      (node (ref "X-NORTH") (pin "19") (pinfunction "19_19") (pintype "bidirectional"))
      (node (ref "X-NORTH") (pin "25") (pinfunction "25_25") (pintype "bidirectional"))
      (node (ref "X-NORTH") (pin "31") (pinfunction "31_31") (pintype "bidirectional"))
      (node (ref "X-NORTH") (pin "37") (pinfunction "37_37") (pintype "bidirectional"))
    )
    (net (code "106") (name "N_VW_CV") (class "Default")
      (node (ref "C8") (pin "1") (pinfunction "1_1") (pintype "passive"))
      (node (ref "R1") (pin "1") (pinfunction "1_1") (pintype "passive"))
      (node (ref "X-NORTH") (pin "2") (pinfunction "2_2") (pintype "bidirectional"))
    )
    (net (code "107") (name "N_VW_OV") (class "Default")
      (node (ref "UNW") (pin "7") (pinfunction "OUTB_7") (pintype "output"))
      (node (ref "X-NORTH") (pin "1") (pinfunction "1_1") (pintype "bidirectional"))
    )
    (net (code "108") (name "N_VW_UV") (class "Default")
      (node (ref "UNW") (pin "1") (pinfunction "OUTA_1") (pintype "output"))
      (node (ref "X-NORTH") (pin "7") (pinfunction "7_7") (pintype "bidirectional"))
    )
    (net (code "109") (name "Net-(SENSORB-CMDN)") (class "Default")
      (node (ref "C61") (pin "1") (pinfunction "1_1") (pintype "passive"))
      (node (ref "SENSOR") (pin "F1") (pinfunction "CMDN_F1") (pintype "bidirectional"))
    )
    (net (code "110") (name "Net-(SENSORB-CMDP)") (class "Default")
      (node (ref "C22") (pin "2") (pinfunction "2_2") (pintype "passive"))
      (node (ref "SENSOR") (pin "F2") (pinfunction "CMDP_F2") (pintype "bidirectional"))
    )
    (net (code "111") (name "Net-(SENSORB-CMDP_COMP)") (class "Default")
      (node (ref "C28") (pin "2") (pinfunction "2_2") (pintype "passive"))
      (node (ref "SENSOR") (pin "H3") (pinfunction "CMDP_COMP_H3") (pintype "bidirectional"))
    )
    (net (code "112") (name "Net-(SENSORB-CMDP_COMP_INV)") (class "Default")
      (node (ref "C27") (pin "2") (pinfunction "2_2") (pintype "passive"))
      (node (ref "SENSOR") (pin "F3") (pinfunction "CMDP_COMP_INV_F3") (pintype "bidirectional"))
    )
    (net (code "113") (name "Net-(SENSORB-CMD_COLAMP)") (class "Default")
      (node (ref "C25") (pin "2") (pinfunction "2_2") (pintype "passive"))
      (node (ref "SENSOR") (pin "C6") (pinfunction "CMD_COLAMP_C6") (pintype "bidirectional"))
    )
    (net (code "114") (name "Net-(SENSORB-CMD_COL_LOAD)") (class "Default")
      (node (ref "C23") (pin "2") (pinfunction "2_2") (pintype "passive"))
      (node (ref "SENSOR") (pin "B1") (pinfunction "CMD_COL_LOAD_B1") (pintype "bidirectional"))
    )
    (net (code "115") (name "Net-(SENSORB-CMD_COL_PC)") (class "Default")
      (node (ref "C26") (pin "2") (pinfunction "2_2") (pintype "passive"))
      (node (ref "SENSOR") (pin "D1") (pinfunction "CMD_COL_PC_D1") (pintype "bidirectional"))
    )
    (net (code "116") (name "Net-(SENSORB-CMD_LVDS)") (class "Default")
      (node (ref "C62") (pin "1") (pinfunction "1_1") (pintype "passive"))
      (node (ref "SENSOR") (pin "C1") (pinfunction "CMD_LVDS_C1") (pintype "bidirectional"))
    )
    (net (code "117") (name "Net-(SENSORB-CMD_RAMP)") (class "Default")
      (node (ref "C24") (pin "2") (pinfunction "2_2") (pintype "passive"))
      (node (ref "SENSOR") (pin "B29") (pinfunction "CMD_RAMP_B29") (pintype "bidirectional"))
    )
    (net (code "118") (name "Net-(SENSORB-VBGAP)") (class "Default")
      (node (ref "C64") (pin "1") (pinfunction "1_1") (pintype "passive"))
      (node (ref "SENSOR") (pin "C29") (pinfunction "VBGAP_C29") (pintype "bidirectional"))
    )
    (net (code "119") (name "Net-(SENSORB-VCLAMP)") (class "Default")
      (node (ref "C63") (pin "1") (pinfunction "1_1") (pintype "passive"))
      (node (ref "SENSOR") (pin "D4") (pinfunction "VCLAMP_D4") (pintype "bidirectional"))
    )
    (net (code "120") (name "Net-(SENSORB-VCLAMP_ADC)") (class "Default")
      (node (ref "C60") (pin "1") (pinfunction "1_1") (pintype "passive"))
      (node (ref "SENSOR") (pin "G2") (pinfunction "VCLAMP_ADC_G2") (pintype "bidirectional"))
    )
    (net (code "121") (name "Net-(SENSORB-VPCH_H)") (class "Default")
      (node (ref "C71") (pin "1") (pinfunction "1_1") (pintype "passive"))
      (node (ref "SENSOR") (pin "C4") (pinfunction "VPCH_H_C4") (pintype "bidirectional"))
    )
    (net (code "122") (name "Net-(SENSORB-VPCH_L)") (class "Default")
      (node (ref "C14") (pin "1") (pinfunction "1_1") (pintype "passive"))
      (node (ref "SENSOR") (pin "A4") (pinfunction "VPCH_L_A4") (pintype "bidirectional"))
    )
    (net (code "123") (name "Net-(SENSORB-VREF)") (class "Default")
      (node (ref "C29") (pin "1") (pinfunction "1_1") (pintype "passive"))
      (node (ref "SENSOR") (pin "A3") (pinfunction "VREF_A3") (pintype "bidirectional"))
    )
    (net (code "124") (name "Net-(SENSORB-VREF_ADC)") (class "Default")
      (node (ref "C30") (pin "1") (pinfunction "1_1") (pintype "passive"))
      (node (ref "SENSOR") (pin "B3") (pinfunction "VREF_ADC_B3") (pintype "bidirectional"))
    )
    (net (code "125") (name "Net-(SENSORB-VRES_L)") (class "Default")
      (node (ref "C15") (pin "1") (pinfunction "1_1") (pintype "passive"))
      (node (ref "SENSOR") (pin "D5") (pinfunction "VRES_L_D5") (pintype "bidirectional"))
    )
    (net (code "126") (name "Net-(SENSORB-VTF_LOW0)") (class "Default")
      (node (ref "C18") (pin "1") (pinfunction "1_1") (pintype "passive"))
      (node (ref "SENSOR") (pin "C5") (pinfunction "VTF_LOW0_C5") (pintype "bidirectional"))
    )
    (net (code "127") (name "Net-(SENSORB-VTF_LOW1)") (class "Default")
      (node (ref "C19") (pin "1") (pinfunction "1_1") (pintype "passive"))
      (node (ref "SENSOR") (pin "D6") (pinfunction "VTF_LOW1_D6") (pintype "bidirectional"))
    )
    (net (code "128") (name "Net-(SENSORB-VTF_LOW2)") (class "Default")
      (node (ref "C20") (pin "1") (pinfunction "1_1") (pintype "passive"))
      (node (ref "SENSOR") (pin "B30") (pinfunction "VTF_LOW2_B30") (pintype "bidirectional"))
    )
    (net (code "129") (name "Net-(SENSORB-VTF_LOW3)") (class "Default")
      (node (ref "C21") (pin "1") (pinfunction "1_1") (pintype "passive"))
      (node (ref "SENSOR") (pin "C30") (pinfunction "VTF_LOW3_C30") (pintype "bidirectional"))
    )
    (net (code "130") (name "Net-(U3-ADJ)") (class "Default")
      (node (ref "R21") (pin "1") (pinfunction "1_1") (pintype "passive"))
      (node (ref "R22") (pin "2") (pinfunction "2_2") (pintype "passive"))
      (node (ref "U3") (pin "5") (pinfunction "ADJ_5") (pintype "input"))
    )
    (net (code "131") (name "Net-(U6-B4)") (class "Default")
      (node (ref "TP9") (pin "TP") (pinfunction "TP_TP") (pintype "input"))
      (node (ref "U6") (pin "9") (pinfunction "B4_9") (pintype "bidirectional"))
    )
    (net (code "132") (name "Net-(UEP-WP)") (class "Default")
      (node (ref "R1X") (pin "2") (pinfunction "2_2") (pintype "passive"))
      (node (ref "R2X") (pin "1") (pinfunction "1_1") (pintype "passive"))
      (node (ref "UEP") (pin "7") (pinfunction "WP_7") (pintype "input"))
    )
    (net (code "133") (name "Net-(UNE-VINA+)") (class "Default")
      (node (ref "R7") (pin "2") (pinfunction "2_2") (pintype "passive"))
      (node (ref "R8") (pin "1") (pinfunction "1_1") (pintype "passive"))
      (node (ref "UNE") (pin "3") (pinfunction "VINA+_3") (pintype "input"))
    )
    (net (code "134") (name "Net-(UNE-VINB-)") (class "Default")
      (node (ref "R8") (pin "2") (pinfunction "2_2") (pintype "passive"))
      (node (ref "R9") (pin "1") (pinfunction "1_1") (pintype "passive"))
      (node (ref "UNE") (pin "6") (pinfunction "VINB-_6") (pintype "input"))
    )
    (net (code "135") (name "Net-(UNN-VINA+)") (class "Default")
      (node (ref "R4") (pin "2") (pinfunction "2_2") (pintype "passive"))
      (node (ref "R5") (pin "1") (pinfunction "1_1") (pintype "passive"))
      (node (ref "UNN") (pin "3") (pinfunction "VINA+_3") (pintype "input"))
    )
    (net (code "136") (name "Net-(UNN-VINB-)") (class "Default")
      (node (ref "R5") (pin "2") (pinfunction "2_2") (pintype "passive"))
      (node (ref "R6") (pin "1") (pinfunction "1_1") (pintype "passive"))
      (node (ref "UNN") (pin "6") (pinfunction "VINB-_6") (pintype "input"))
    )
    (net (code "137") (name "Net-(UNW-VINA+)") (class "Default")
      (node (ref "R1") (pin "2") (pinfunction "2_2") (pintype "passive"))
      (node (ref "R2") (pin "1") (pinfunction "1_1") (pintype "passive"))
      (node (ref "UNW") (pin "3") (pinfunction "VINA+_3") (pintype "input"))
    )
    (net (code "138") (name "Net-(UNW-VINB-)") (class "Default")
      (node (ref "R2") (pin "2") (pinfunction "2_2") (pintype "passive"))
      (node (ref "R3") (pin "1") (pinfunction "1_1") (pintype "passive"))
      (node (ref "UNW") (pin "6") (pinfunction "VINB-_6") (pintype "input"))
    )
    (net (code "139") (name "Net-(USE-VINA+)") (class "Default")
      (node (ref "R10") (pin "2") (pinfunction "2_2") (pintype "passive"))
      (node (ref "R11") (pin "1") (pinfunction "1_1") (pintype "passive"))
      (node (ref "USE") (pin "3") (pinfunction "VINA+_3") (pintype "input"))
    )
    (net (code "140") (name "Net-(USE-VINB-)") (class "Default")
      (node (ref "R11") (pin "2") (pinfunction "2_2") (pintype "passive"))
      (node (ref "R12") (pin "1") (pinfunction "1_1") (pintype "passive"))
      (node (ref "USE") (pin "6") (pinfunction "VINB-_6") (pintype "input"))
    )
    (net (code "141") (name "Net-(USS-VINA+)") (class "Default")
      (node (ref "R13") (pin "2") (pinfunction "2_2") (pintype "passive"))
      (node (ref "R14") (pin "1") (pinfunction "1_1") (pintype "passive"))
      (node (ref "USS") (pin "3") (pinfunction "VINA+_3") (pintype "input"))
    )
    (net (code "142") (name "Net-(USS-VINB-)") (class "Default")
      (node (ref "R14") (pin "2") (pinfunction "2_2") (pintype "passive"))
      (node (ref "R15") (pin "1") (pinfunction "1_1") (pintype "passive"))
      (node (ref "USS") (pin "6") (pinfunction "VINB-_6") (pintype "input"))
    )
    (net (code "143") (name "Net-(USW-VINA+)") (class "Default")
      (node (ref "R16") (pin "2") (pinfunction "2_2") (pintype "passive"))
      (node (ref "R17") (pin "1") (pinfunction "1_1") (pintype "passive"))
      (node (ref "USW") (pin "3") (pinfunction "VINA+_3") (pintype "input"))
    )
    (net (code "144") (name "Net-(USW-VINB-)") (class "Default")
      (node (ref "R17") (pin "2") (pinfunction "2_2") (pintype "passive"))
      (node (ref "R18") (pin "1") (pinfunction "1_1") (pintype "passive"))
      (node (ref "USW") (pin "6") (pinfunction "VINB-_6") (pintype "input"))
    )
    (net (code "145") (name "S00_N") (class "Default")
      (node (ref "X-SOUTH") (pin "16") (pinfunction "16_16") (pintype "bidirectional"))
    )
    (net (code "146") (name "S00_P") (class "Default")
      (node (ref "X-SOUTH") (pin "14") (pinfunction "14_14") (pintype "bidirectional"))
    )
    (net (code "147") (name "S01_N") (class "Default")
      (node (ref "X-SOUTH") (pin "17") (pinfunction "17_17") (pintype "bidirectional"))
    )
    (net (code "148") (name "S01_P") (class "Default")
      (node (ref "X-SOUTH") (pin "15") (pinfunction "15_15") (pintype "bidirectional"))
    )
    (net (code "149") (name "S02_N") (class "Default")
      (node (ref "X-SOUTH") (pin "22") (pinfunction "22_22") (pintype "bidirectional"))
    )
    (net (code "150") (name "S02_P") (class "Default")
      (node (ref "X-SOUTH") (pin "20") (pinfunction "20_20") (pintype "bidirectional"))
    )
    (net (code "151") (name "S03_N") (class "Default")
      (node (ref "X-SOUTH") (pin "23") (pinfunction "23_23") (pintype "bidirectional"))
    )
    (net (code "152") (name "S03_P") (class "Default")
      (node (ref "X-SOUTH") (pin "21") (pinfunction "21_21") (pintype "bidirectional"))
    )
    (net (code "153") (name "S04_N") (class "Default")
      (node (ref "SENSOR") (pin "C24") (pinfunction "OUT32_N_C24") (pintype "output"))
      (node (ref "X-SOUTH") (pin "28") (pinfunction "28_28") (pintype "bidirectional"))
    )
    (net (code "154") (name "S04_P") (class "Default")
      (node (ref "SENSOR") (pin "C25") (pinfunction "OUT32_P_C25") (pintype "output"))
      (node (ref "X-SOUTH") (pin "26") (pinfunction "26_26") (pintype "bidirectional"))
    )
    (net (code "155") (name "S05_N") (class "Default")
      (node (ref "X-SOUTH") (pin "29") (pinfunction "29_29") (pintype "bidirectional"))
    )
    (net (code "156") (name "S05_P") (class "Default")
      (node (ref "X-SOUTH") (pin "27") (pinfunction "27_27") (pintype "bidirectional"))
    )
    (net (code "157") (name "S06_N") (class "Default")
      (node (ref "SENSOR") (pin "D23") (pinfunction "OUT30_N_D23") (pintype "output"))
      (node (ref "X-SOUTH") (pin "34") (pinfunction "34_34") (pintype "bidirectional"))
    )
    (net (code "158") (name "S06_P") (class "Default")
      (node (ref "SENSOR") (pin "D24") (pinfunction "OUT30_P_D24") (pintype "output"))
      (node (ref "X-SOUTH") (pin "32") (pinfunction "32_32") (pintype "bidirectional"))
    )
    (net (code "159") (name "S07_N") (class "Default")
      (node (ref "SENSOR") (pin "B24") (pinfunction "OUT31_N_B24") (pintype "output"))
      (node (ref "X-SOUTH") (pin "35") (pinfunction "35_35") (pintype "bidirectional"))
    )
    (net (code "160") (name "S07_P") (class "Default")
      (node (ref "SENSOR") (pin "B25") (pinfunction "OUT31_P_B25") (pintype "output"))
      (node (ref "X-SOUTH") (pin "33") (pinfunction "33_33") (pintype "bidirectional"))
    )
    (net (code "161") (name "S08_N") (class "Default")
      (node (ref "SENSOR") (pin "D21") (pinfunction "OUT27_N_D21") (pintype "output"))
      (node (ref "X-SOUTH") (pin "40") (pinfunction "40_40") (pintype "bidirectional"))
    )
    (net (code "162") (name "S08_P") (class "Default")
      (node (ref "SENSOR") (pin "D22") (pinfunction "OUT27_P_D22") (pintype "output"))
      (node (ref "X-SOUTH") (pin "38") (pinfunction "38_38") (pintype "bidirectional"))
    )
    (net (code "163") (name "S09_N") (class "Default")
      (node (ref "SENSOR") (pin "A23") (pinfunction "OUT29_N_A23") (pintype "output"))
      (node (ref "X-SOUTH") (pin "41") (pinfunction "41_41") (pintype "bidirectional"))
    )
    (net (code "164") (name "S09_P") (class "Default")
      (node (ref "SENSOR") (pin "A24") (pinfunction "OUT29_P_A24") (pintype "output"))
      (node (ref "X-SOUTH") (pin "39") (pinfunction "39_39") (pintype "bidirectional"))
    )
    (net (code "165") (name "S10_N") (class "Default")
      (node (ref "SENSOR") (pin "C21") (pinfunction "OUT28_N_C21") (pintype "output"))
      (node (ref "X-SOUTH") (pin "46") (pinfunction "46_46") (pintype "bidirectional"))
    )
    (net (code "166") (name "S10_P") (class "Default")
      (node (ref "SENSOR") (pin "C22") (pinfunction "OUT28_P_C22") (pintype "output"))
      (node (ref "X-SOUTH") (pin "44") (pinfunction "44_44") (pintype "bidirectional"))
    )
    (net (code "167") (name "S11_N") (class "Default")
      (node (ref "SENSOR") (pin "B20") (pinfunction "OUT26_N_B20") (pintype "output"))
      (node (ref "X-SOUTH") (pin "47") (pinfunction "47_47") (pintype "bidirectional"))
    )
    (net (code "168") (name "S11_P") (class "Default")
      (node (ref "SENSOR") (pin "B21") (pinfunction "OUT26_P_B21") (pintype "output"))
      (node (ref "X-SOUTH") (pin "45") (pinfunction "45_45") (pintype "bidirectional"))
    )
    (net (code "169") (name "S12_N") (class "Default")
      (node (ref "SENSOR") (pin "D19") (pinfunction "OUT24_N_D19") (pintype "output"))
      (node (ref "X-SOUTH") (pin "52") (pinfunction "52_52") (pintype "bidirectional"))
    )
    (net (code "170") (name "S12_P") (class "Default")
      (node (ref "SENSOR") (pin "D20") (pinfunction "OUT24_P_D20") (pintype "output"))
      (node (ref "X-SOUTH") (pin "50") (pinfunction "50_50") (pintype "bidirectional"))
    )
    (net (code "171") (name "S13_N") (class "Default")
      (node (ref "SENSOR") (pin "A19") (pinfunction "OUT23_N_A19") (pintype "output"))
      (node (ref "X-SOUTH") (pin "53") (pinfunction "53_53") (pintype "bidirectional"))
    )
    (net (code "172") (name "S13_P") (class "Default")
      (node (ref "SENSOR") (pin "A20") (pinfunction "OUT23_P_A20") (pintype "output"))
      (node (ref "X-SOUTH") (pin "51") (pinfunction "51_51") (pintype "bidirectional"))
    )
    (net (code "173") (name "S14_N") (class "Default")
      (node (ref "SENSOR") (pin "C19") (pinfunction "OUT25_N_C19") (pintype "output"))
      (node (ref "X-SOUTH") (pin "58") (pinfunction "58_58") (pintype "bidirectional"))
    )
    (net (code "174") (name "S14_P") (class "Default")
      (node (ref "SENSOR") (pin "C20") (pinfunction "OUT25_P_C20") (pintype "output"))
      (node (ref "X-SOUTH") (pin "56") (pinfunction "56_56") (pintype "bidirectional"))
    )
    (net (code "175") (name "S15_N") (class "Default")
      (node (ref "SENSOR") (pin "B18") (pinfunction "OUT22_N_B18") (pintype "output"))
      (node (ref "X-SOUTH") (pin "59") (pinfunction "59_59") (pintype "bidirectional"))
    )
    (net (code "176") (name "S15_P") (class "Default")
      (node (ref "SENSOR") (pin "B19") (pinfunction "OUT22_P_B19") (pintype "output"))
      (node (ref "X-SOUTH") (pin "57") (pinfunction "57_57") (pintype "bidirectional"))
    )
    (net (code "177") (name "S16_N") (class "Default")
      (node (ref "SENSOR") (pin "C17") (pinfunction "OUT21_N_C17") (pintype "output"))
      (node (ref "X-SOUTH") (pin "64") (pinfunction "64_64") (pintype "bidirectional"))
    )
    (net (code "178") (name "S16_P") (class "Default")
      (node (ref "SENSOR") (pin "C18") (pinfunction "OUT21_P_C18") (pintype "output"))
      (node (ref "X-SOUTH") (pin "62") (pinfunction "62_62") (pintype "bidirectional"))
    )
    (net (code "179") (name "S17_N") (class "Default")
      (node (ref "SENSOR") (pin "A17") (pinfunction "OUT19_N_A17") (pintype "output"))
      (node (ref "X-SOUTH") (pin "65") (pinfunction "65_65") (pintype "bidirectional"))
    )
    (net (code "180") (name "S17_P") (class "Default")
      (node (ref "SENSOR") (pin "A18") (pinfunction "OUT19_P_A18") (pintype "output"))
      (node (ref "X-SOUTH") (pin "63") (pinfunction "63_63") (pintype "bidirectional"))
    )
    (net (code "181") (name "S18_N") (class "Default")
      (node (ref "SENSOR") (pin "D17") (pinfunction "OUT20_N_D17") (pintype "output"))
      (node (ref "X-SOUTH") (pin "70") (pinfunction "70_70") (pintype "bidirectional"))
    )
    (net (code "182") (name "S18_P") (class "Default")
      (node (ref "SENSOR") (pin "D18") (pinfunction "OUT20_P_D18") (pintype "output"))
      (node (ref "X-SOUTH") (pin "68") (pinfunction "68_68") (pintype "bidirectional"))
    )
    (net (code "183") (name "S19_N") (class "Default")
      (node (ref "SENSOR") (pin "B16") (pinfunction "OUT18_N_B16") (pintype "output"))
      (node (ref "X-SOUTH") (pin "71") (pinfunction "71_71") (pintype "bidirectional"))
    )
    (net (code "184") (name "S19_P") (class "Default")
      (node (ref "SENSOR") (pin "B17") (pinfunction "OUT18_P_B17") (pintype "output"))
      (node (ref "X-SOUTH") (pin "69") (pinfunction "69_69") (pintype "bidirectional"))
    )
    (net (code "185") (name "S20_N") (class "Default")
      (node (ref "SENSOR") (pin "D15") (pinfunction "OUT17_N_D15") (pintype "output"))
      (node (ref "X-SOUTH") (pin "76") (pinfunction "76_76") (pintype "bidirectional"))
    )
    (net (code "186") (name "S20_P") (class "Default")
      (node (ref "SENSOR") (pin "D16") (pinfunction "OUT17_P_D16") (pintype "output"))
      (node (ref "X-SOUTH") (pin "74") (pinfunction "74_74") (pintype "bidirectional"))
    )
    (net (code "187") (name "S21_N") (class "Default")
      (node (ref "SENSOR") (pin "B14") (pinfunction "OUT16_N_B14") (pintype "output"))
      (node (ref "X-SOUTH") (pin "77") (pinfunction "77_77") (pintype "bidirectional"))
    )
    (net (code "188") (name "S21_P") (class "Default")
      (node (ref "SENSOR") (pin "B15") (pinfunction "OUT16_P_B15") (pintype "output"))
      (node (ref "X-SOUTH") (pin "75") (pinfunction "75_75") (pintype "bidirectional"))
    )
    (net (code "189") (name "S22_N") (class "Default")
      (node (ref "SENSOR") (pin "D13") (pinfunction "OUT15_N_D13") (pintype "output"))
      (node (ref "X-SOUTH") (pin "82") (pinfunction "82_82") (pintype "bidirectional"))
    )
    (net (code "190") (name "S22_P") (class "Default")
      (node (ref "SENSOR") (pin "D14") (pinfunction "OUT15_P_D14") (pintype "output"))
      (node (ref "X-SOUTH") (pin "80") (pinfunction "80_80") (pintype "bidirectional"))
    )
    (net (code "191") (name "S23_N") (class "Default")
      (node (ref "SENSOR") (pin "A13") (pinfunction "OUT13_N_A13") (pintype "output"))
      (node (ref "X-SOUTH") (pin "83") (pinfunction "83_83") (pintype "bidirectional"))
    )
    (net (code "192") (name "S23_P") (class "Default")
      (node (ref "SENSOR") (pin "A14") (pinfunction "OUT13_P_A14") (pintype "output"))
      (node (ref "X-SOUTH") (pin "81") (pinfunction "81_81") (pintype "bidirectional"))
    )
    (net (code "193") (name "S24_N") (class "Default")
      (node (ref "SENSOR") (pin "C13") (pinfunction "OUT14_N_C13") (pintype "output"))
      (node (ref "X-SOUTH") (pin "88") (pinfunction "88_88") (pintype "bidirectional"))
    )
    (net (code "194") (name "S24_P") (class "Default")
      (node (ref "SENSOR") (pin "C14") (pinfunction "OUT14_P_C14") (pintype "output"))
      (node (ref "X-SOUTH") (pin "86") (pinfunction "86_86") (pintype "bidirectional"))
    )
    (net (code "195") (name "S25_N") (class "Default")
      (node (ref "SENSOR") (pin "B12") (pinfunction "OUT12_N_B12") (pintype "output"))
      (node (ref "X-SOUTH") (pin "89") (pinfunction "89_89") (pintype "bidirectional"))
    )
    (net (code "196") (name "S25_P") (class "Default")
      (node (ref "SENSOR") (pin "B13") (pinfunction "OUT12_P_B13") (pintype "output"))
      (node (ref "X-SOUTH") (pin "87") (pinfunction "87_87") (pintype "bidirectional"))
    )
    (net (code "197") (name "S26_N") (class "Default")
      (node (ref "SENSOR") (pin "D11") (pinfunction "OUT10_N_D11") (pintype "output"))
      (node (ref "X-SOUTH") (pin "94") (pinfunction "94_94") (pintype "bidirectional"))
    )
    (net (code "198") (name "S26_P") (class "Default")
      (node (ref "SENSOR") (pin "D12") (pinfunction "OUT10_P_D12") (pintype "output"))
      (node (ref "X-SOUTH") (pin "92") (pinfunction "92_92") (pintype "bidirectional"))
    )
    (net (code "199") (name "S27_N") (class "Default")
      (node (ref "SENSOR") (pin "A11") (pinfunction "OUT9_N_A11") (pintype "output"))
      (node (ref "X-SOUTH") (pin "95") (pinfunction "95_95") (pintype "bidirectional"))
    )
    (net (code "200") (name "S27_P") (class "Default")
      (node (ref "SENSOR") (pin "A12") (pinfunction "OUT9_P_A12") (pintype "output"))
      (node (ref "X-SOUTH") (pin "93") (pinfunction "93_93") (pintype "bidirectional"))
    )
    (net (code "201") (name "S28_N") (class "Default")
      (node (ref "SENSOR") (pin "C11") (pinfunction "OUT11_N_C11") (pintype "output"))
      (node (ref "X-SOUTH") (pin "100") (pinfunction "100_100") (pintype "bidirectional"))
    )
    (net (code "202") (name "S28_P") (class "Default")
      (node (ref "SENSOR") (pin "C12") (pinfunction "OUT11_P_C12") (pintype "output"))
      (node (ref "X-SOUTH") (pin "98") (pinfunction "98_98") (pintype "bidirectional"))
    )
    (net (code "203") (name "S29_N") (class "Default")
      (node (ref "SENSOR") (pin "B10") (pinfunction "OUT8_N_B10") (pintype "output"))
      (node (ref "X-SOUTH") (pin "101") (pinfunction "101_101") (pintype "bidirectional"))
    )
    (net (code "204") (name "S29_P") (class "Default")
      (node (ref "SENSOR") (pin "B11") (pinfunction "OUT8_P_B11") (pintype "output"))
      (node (ref "X-SOUTH") (pin "99") (pinfunction "99_99") (pintype "bidirectional"))
    )
    (net (code "205") (name "S30_N") (class "Default")
      (node (ref "SENSOR") (pin "C9") (pinfunction "OUT7_N_C9") (pintype "output"))
      (node (ref "X-SOUTH") (pin "106") (pinfunction "106_106") (pintype "bidirectional"))
    )
    (net (code "206") (name "S30_P") (class "Default")
      (node (ref "SENSOR") (pin "C10") (pinfunction "OUT7_P_C10") (pintype "output"))
      (node (ref "X-SOUTH") (pin "104") (pinfunction "104_104") (pintype "bidirectional"))
    )
    (net (code "207") (name "S31_N") (class "Default")
      (node (ref "SENSOR") (pin "B8") (pinfunction "OUT5_N_B8") (pintype "output"))
      (node (ref "X-SOUTH") (pin "107") (pinfunction "107_107") (pintype "bidirectional"))
    )
    (net (code "208") (name "S31_P") (class "Default")
      (node (ref "SENSOR") (pin "B9") (pinfunction "OUT5_P_B9") (pintype "output"))
      (node (ref "X-SOUTH") (pin "105") (pinfunction "105_105") (pintype "bidirectional"))
    )
    (net (code "209") (name "S32_N") (class "Default")
      (node (ref "SENSOR") (pin "D9") (pinfunction "OUT6_N_D9") (pintype "output"))
      (node (ref "X-SOUTH") (pin "112") (pinfunction "112_112") (pintype "bidirectional"))
    )
    (net (code "210") (name "S32_P") (class "Default")
      (node (ref "SENSOR") (pin "D10") (pinfunction "OUT6_P_D10") (pintype "output"))
      (node (ref "X-SOUTH") (pin "110") (pinfunction "110_110") (pintype "bidirectional"))
    )
    (net (code "211") (name "S33_N") (class "Default")
      (node (ref "SENSOR") (pin "A7") (pinfunction "OUT2_N_A7") (pintype "output"))
      (node (ref "X-SOUTH") (pin "113") (pinfunction "113_113") (pintype "bidirectional"))
    )
    (net (code "212") (name "S33_P") (class "Default")
      (node (ref "SENSOR") (pin "A8") (pinfunction "OUT2_P_A8") (pintype "output"))
      (node (ref "X-SOUTH") (pin "111") (pinfunction "111_111") (pintype "bidirectional"))
    )
    (net (code "213") (name "S34_N") (class "Default")
      (node (ref "SENSOR") (pin "C7") (pinfunction "OUT4_N_C7") (pintype "output"))
      (node (ref "X-SOUTH") (pin "118") (pinfunction "118_118") (pintype "bidirectional"))
    )
    (net (code "214") (name "S34_P") (class "Default")
      (node (ref "SENSOR") (pin "C8") (pinfunction "OUT4_P_C8") (pintype "output"))
      (node (ref "X-SOUTH") (pin "116") (pinfunction "116_116") (pintype "bidirectional"))
    )
    (net (code "215") (name "S35_N") (class "Default")
      (node (ref "SENSOR") (pin "B6") (pinfunction "OUT1_N_B6") (pintype "output"))
      (node (ref "X-SOUTH") (pin "119") (pinfunction "119_119") (pintype "bidirectional"))
    )
    (net (code "216") (name "S35_P") (class "Default")
      (node (ref "SENSOR") (pin "B7") (pinfunction "OUT1_P_B7") (pintype "output"))
      (node (ref "X-SOUTH") (pin "117") (pinfunction "117_117") (pintype "bidirectional"))
    )
    (net (code "217") (name "S36_N") (class "Default")
      (node (ref "SENSOR") (pin "D7") (pinfunction "OUT3_N_D7") (pintype "output"))
      (node (ref "X-SOUTH") (pin "124") (pinfunction "124_124") (pintype "bidirectional"))
    )
    (net (code "218") (name "S36_P") (class "Default")
      (node (ref "SENSOR") (pin "D8") (pinfunction "OUT3_P_D8") (pintype "output"))
      (node (ref "X-SOUTH") (pin "122") (pinfunction "122_122") (pintype "bidirectional"))
    )
    (net (code "219") (name "S37_N") (class "Default")
      (node (ref "SENSOR") (pin "A5") (pinfunction "OUTCTR_N_A5") (pintype "output"))
      (node (ref "X-SOUTH") (pin "125") (pinfunction "125_125") (pintype "bidirectional"))
    )
    (net (code "220") (name "S37_P") (class "Default")
      (node (ref "SENSOR") (pin "A6") (pinfunction "OUTCTR_P_A6") (pintype "output"))
      (node (ref "X-SOUTH") (pin "123") (pinfunction "123_123") (pintype "bidirectional"))
    )
    (net (code "221") (name "S38_N") (class "Default")
      (node (ref "X-SOUTH") (pin "130") (pinfunction "130_130") (pintype "bidirectional"))
    )
    (net (code "222") (name "S38_P") (class "Default")
      (node (ref "X-SOUTH") (pin "128") (pinfunction "128_128") (pintype "bidirectional"))
    )
    (net (code "223") (name "S39_N") (class "Default")
      (node (ref "U3") (pin "6") (pinfunction "EN_6") (pintype "input"))
      (node (ref "X-SOUTH") (pin "131") (pinfunction "131_131") (pintype "bidirectional"))
    )
    (net (code "224") (name "S39_P") (class "Default")
      (node (ref "X-SOUTH") (pin "129") (pinfunction "129_129") (pintype "bidirectional"))
    )
    (net (code "225") (name "SPI_CLK") (class "Default")
      (node (ref "SENSOR") (pin "H29") (pinfunction "SPI_CLK_H29") (pintype "input"))
      (node (ref "U4") (pin "9") (pinfunction "B4_9") (pintype "bidirectional"))
    )
    (net (code "226") (name "SPI_EN") (class "Default")
      (node (ref "SENSOR") (pin "F28") (pinfunction "SPI_EN_F28") (pintype "input"))
      (node (ref "U4") (pin "12") (pinfunction "B1_12") (pintype "bidirectional"))
    )
    (net (code "227") (name "SPI_IN") (class "Default")
      (node (ref "SENSOR") (pin "E28") (pinfunction "SPI_IN_E28") (pintype "input"))
      (node (ref "U4") (pin "10") (pinfunction "B3_10") (pintype "bidirectional"))
    )
    (net (code "228") (name "SPI_OUT") (class "Default")
      (node (ref "SENSOR") (pin "G28") (pinfunction "SPI_OUT_G28") (pintype "output"))
      (node (ref "U4") (pin "11") (pinfunction "B2_11") (pintype "bidirectional"))
    )
    (net (code "229") (name "SYS_RES_N") (class "Default")
      (node (ref "SENSOR") (pin "F30") (pinfunction "SYS_RES_N_F30") (pintype "input"))
      (node (ref "U5") (pin "10") (pinfunction "B3_10") (pintype "bidirectional"))
    )
    (net (code "230") (name "S_CHK_EN") (class "Default")
      (node (ref "X-SOUTH") (pin "8") (pinfunction "8_8") (pintype "bidirectional"))
    )
    (net (code "231") (name "S_CHK_V") (class "Default")
      (node (ref "C5") (pin "1") (pinfunction "1_1") (pintype "passive"))
      (node (ref "C6") (pin "1") (pinfunction "1_1") (pintype "passive"))
      (node (ref "C7") (pin "1") (pinfunction "1_1") (pintype "passive"))
      (node (ref "R20") (pin "1") (pinfunction "1_1") (pintype "passive"))
      (node (ref "TP3") (pin "TP") (pinfunction "TP_TP") (pintype "input"))
      (node (ref "USE") (pin "8") (pinfunction "VDD_8") (pintype "power_in"))
      (node (ref "USS") (pin "8") (pinfunction "VDD_8") (pintype "power_in"))
      (node (ref "USW") (pin "8") (pinfunction "VDD_8") (pintype "power_in"))
      (node (ref "X-SOUTH") (pin "10") (pinfunction "10_10") (pintype "bidirectional"))
    )
    (net (code "232") (name "S_I2C_EN") (class "Default")
      (node (ref "X-SOUTH") (pin "137") (pinfunction "137_137") (pintype "bidirectional"))
    )
    (net (code "233") (name "S_I2C_V") (class "Default")
      (node (ref "U7") (pin "8") (pinfunction "VCC_8") (pintype "power_in"))
      (node (ref "X-SOUTH") (pin "135") (pinfunction "135_135") (pintype "bidirectional"))
    )
    (net (code "234") (name "S_REF") (class "Default")
      (node (ref "R20") (pin "2") (pinfunction "2_2") (pintype "passive"))
      (node (ref "TP4") (pin "TP") (pinfunction "TP_TP") (pintype "input"))
      (node (ref "U2") (pin "1") (pinfunction "CATHODE_1") (pintype "output"))
      (node (ref "U2") (pin "3") (pinfunction "REF_3") (pintype "input"))
      (node (ref "USE") (pin "2") (pinfunction "VINA-_2") (pintype "input"))
      (node (ref "USE") (pin "5") (pinfunction "VINB+_5") (pintype "input"))
      (node (ref "USS") (pin "2") (pinfunction "VINA-_2") (pintype "input"))
      (node (ref "USS") (pin "5") (pinfunction "VINB+_5") (pintype "input"))
      (node (ref "USW") (pin "2") (pinfunction "VINA-_2") (pintype "input"))
      (node (ref "USW") (pin "5") (pinfunction "VINB+_5") (pintype "input"))
    )
    (net (code "235") (name "S_SCK") (class "Default")
      (node (ref "X-SOUTH") (pin "144") (pinfunction "144_144") (pintype "bidirectional"))
    )
    (net (code "236") (name "S_SCL") (class "Default")
      (node (ref "U7") (pin "2") (pinfunction "SCL_2") (pintype "input"))
      (node (ref "X-SOUTH") (pin "143") (pinfunction "143_143") (pintype "bidirectional"))
    )
    (net (code "237") (name "S_SDA") (class "Default")
      (node (ref "U7") (pin "1") (pinfunction "SDA_1") (pintype "bidirectional"))
      (node (ref "X-SOUTH") (pin "141") (pinfunction "141_141") (pintype "bidirectional"))
    )
    (net (code "238") (name "S_SDI") (class "Default")
      (node (ref "X-SOUTH") (pin "140") (pinfunction "140_140") (pintype "bidirectional"))
    )
    (net (code "239") (name "S_SDO") (class "Default")
      (node (ref "X-SOUTH") (pin "142") (pinfunction "142_142") (pintype "bidirectional"))
    )
    (net (code "240") (name "S_SPI_EN") (class "Default")
      (node (ref "X-SOUTH") (pin "136") (pinfunction "136_136") (pintype "bidirectional"))
    )
    (net (code "241") (name "S_SPI_V") (class "Default")
      (node (ref "X-SOUTH") (pin "134") (pinfunction "134_134") (pintype "bidirectional"))
    )
    (net (code "242") (name "S_VE") (class "Default")
      (node (ref "X-SOUTH") (pin "13") (pinfunction "13_13") (pintype "bidirectional"))
      (node (ref "X-SOUTH") (pin "19") (pinfunction "19_19") (pintype "bidirectional"))
      (node (ref "X-SOUTH") (pin "25") (pinfunction "25_25") (pintype "bidirectional"))
      (node (ref "X-SOUTH") (pin "31") (pinfunction "31_31") (pintype "bidirectional"))
      (node (ref "X-SOUTH") (pin "37") (pinfunction "37_37") (pintype "bidirectional"))
    )
    (net (code "243") (name "S_VE_CV") (class "Default")
      (node (ref "C11") (pin "1") (pinfunction "1_1") (pintype "passive"))
      (node (ref "R10") (pin "1") (pinfunction "1_1") (pintype "passive"))
      (node (ref "X-SOUTH") (pin "2") (pinfunction "2_2") (pintype "bidirectional"))
    )
    (net (code "244") (name "S_VE_OV") (class "Default")
      (node (ref "USE") (pin "7") (pinfunction "OUTB_7") (pintype "output"))
      (node (ref "X-SOUTH") (pin "1") (pinfunction "1_1") (pintype "bidirectional"))
    )
    (net (code "245") (name "S_VE_UV") (class "Default")
      (node (ref "USE") (pin "1") (pinfunction "OUTA_1") (pintype "output"))
      (node (ref "X-SOUTH") (pin "7") (pinfunction "7_7") (pintype "bidirectional"))
    )
    (net (code "246") (name "S_VS") (class "Default")
      (node (ref "C45") (pin "1") (pinfunction "1_1") (pintype "passive"))
      (node (ref "C46") (pin "1") (pinfunction "1_1") (pintype "passive"))
      (node (ref "C47") (pin "1") (pinfunction "1_1") (pintype "passive"))
      (node (ref "C48") (pin "1") (pinfunction "1_1") (pintype "passive"))
      (node (ref "C49") (pin "1") (pinfunction "1_1") (pintype "passive"))
      (node (ref "C72") (pin "1") (pinfunction "1_1") (pintype "passive"))
      (node (ref "C73") (pin "1") (pinfunction "1_1") (pintype "passive"))
      (node (ref "C74") (pin "1") (pinfunction "1_1") (pintype "passive"))
      (node (ref "C81") (pin "1") (pinfunction "1_1") (pintype "passive"))
      (node (ref "C82") (pin "1") (pinfunction "1_1") (pintype "passive"))
      (node (ref "C83") (pin "1") (pinfunction "1_1") (pintype "passive"))
      (node (ref "SENSOR") (pin "A30") (pinfunction "VDD_PIX_A30") (pintype "power_in"))
      (node (ref "SENSOR") (pin "D28") (pinfunction "VDD_PIX_D28") (pintype "power_in"))
      (node (ref "SENSOR") (pin "D30") (pinfunction "VDD_PIX_D30") (pintype "power_in"))
      (node (ref "SENSOR") (pin "G1") (pinfunction "VDD_PIX_G1") (pintype "power_in"))
      (node (ref "SENSOR") (pin "H28") (pinfunction "VDD_PIX_H28") (pintype "power_in"))
      (node (ref "TP6") (pin "TP") (pinfunction "TP_TP") (pintype "input"))
      (node (ref "X-SOUTH") (pin "49") (pinfunction "49_49") (pintype "bidirectional"))
      (node (ref "X-SOUTH") (pin "55") (pinfunction "55_55") (pintype "bidirectional"))
      (node (ref "X-SOUTH") (pin "61") (pinfunction "61_61") (pintype "bidirectional"))
      (node (ref "X-SOUTH") (pin "67") (pinfunction "67_67") (pintype "bidirectional"))
      (node (ref "X-SOUTH") (pin "73") (pinfunction "73_73") (pintype "bidirectional"))
      (node (ref "X-SOUTH") (pin "79") (pinfunction "79_79") (pintype "bidirectional"))
      (node (ref "X-SOUTH") (pin "85") (pinfunction "85_85") (pintype "bidirectional"))
      (node (ref "X-SOUTH") (pin "91") (pinfunction "91_91") (pintype "bidirectional"))
      (node (ref "X-SOUTH") (pin "97") (pinfunction "97_97") (pintype "bidirectional"))
    )
    (net (code "247") (name "S_VS_CV") (class "Default")
      (node (ref "C12") (pin "1") (pinfunction "1_1") (pintype "passive"))
      (node (ref "R13") (pin "1") (pinfunction "1_1") (pintype "passive"))
      (node (ref "X-SOUTH") (pin "4") (pinfunction "4_4") (pintype "bidirectional"))
    )
    (net (code "248") (name "S_VS_OV") (class "Default")
      (node (ref "USS") (pin "7") (pinfunction "OUTB_7") (pintype "output"))
      (node (ref "X-SOUTH") (pin "3") (pinfunction "3_3") (pintype "bidirectional"))
    )
    (net (code "249") (name "S_VS_UV") (class "Default")
      (node (ref "USS") (pin "1") (pinfunction "OUTA_1") (pintype "output"))
      (node (ref "X-SOUTH") (pin "9") (pinfunction "9_9") (pintype "bidirectional"))
    )
    (net (code "250") (name "S_VW") (class "Default")
      (node (ref "C90") (pin "1") (pinfunction "1_1") (pintype "passive"))
      (node (ref "U3") (pin "1") (pinfunction "BIAS_1") (pintype "power_in"))
      (node (ref "U3") (pin "3") (pinfunction "IN_3") (pintype "power_in"))
      (node (ref "X-SOUTH") (pin "109") (pinfunction "109_109") (pintype "bidirectional"))
      (node (ref "X-SOUTH") (pin "115") (pinfunction "115_115") (pintype "bidirectional"))
      (node (ref "X-SOUTH") (pin "121") (pinfunction "121_121") (pintype "bidirectional"))
      (node (ref "X-SOUTH") (pin "127") (pinfunction "127_127") (pintype "bidirectional"))
      (node (ref "X-SOUTH") (pin "133") (pinfunction "133_133") (pintype "bidirectional"))
    )
    (net (code "251") (name "S_VW_CV") (class "Default")
      (node (ref "C13") (pin "1") (pinfunction "1_1") (pintype "passive"))
      (node (ref "R16") (pin "1") (pinfunction "1_1") (pintype "passive"))
      (node (ref "X-SOUTH") (pin "6") (pinfunction "6_6") (pintype "bidirectional"))
    )
    (net (code "252") (name "S_VW_OV") (class "Default")
      (node (ref "USW") (pin "7") (pinfunction "OUTB_7") (pintype "output"))
      (node (ref "X-SOUTH") (pin "5") (pinfunction "5_5") (pintype "bidirectional"))
    )
    (net (code "253") (name "S_VW_UV") (class "Default")
      (node (ref "USW") (pin "1") (pinfunction "OUTA_1") (pintype "output"))
      (node (ref "X-SOUTH") (pin "11") (pinfunction "11_11") (pintype "bidirectional"))
    )
    (net (code "254") (name "TDIG1") (class "Default")
      (node (ref "SENSOR") (pin "G27") (pinfunction "TDIG1_G27") (pintype "output"))
      (node (ref "U5") (pin "9") (pinfunction "B4_9") (pintype "bidirectional"))
    )
    (net (code "255") (name "TDIG2") (class "Default")
      (node (ref "SENSOR") (pin "G26") (pinfunction "TDIG2_G26") (pintype "output"))
      (node (ref "U6") (pin "11") (pinfunction "B2_11") (pintype "bidirectional"))
    )
    (net (code "256") (name "T_EXP1") (class "Default")
      (node (ref "SENSOR") (pin "H30") (pinfunction "T_EXP1_H30") (pintype "input"))
      (node (ref "U5") (pin "12") (pinfunction "B1_12") (pintype "bidirectional"))
    )
    (net (code "257") (name "T_EXP2") (class "Default")
      (node (ref "SENSOR") (pin "E29") (pinfunction "T_EXP2_E29") (pintype "input"))
      (node (ref "U6") (pin "10") (pinfunction "B3_10") (pintype "bidirectional"))
    )
    (net (code "258") (name "VRAMP1") (class "Default")
      (node (ref "C16") (pin "1") (pinfunction "1_1") (pintype "passive"))
      (node (ref "R23") (pin "1") (pinfunction "1_1") (pintype "passive"))
      (node (ref "SENSOR") (pin "G29") (pinfunction "VRAMP1_G29") (pintype "bidirectional"))
    )
    (net (code "259") (name "VRAMP2") (class "Default")
      (node (ref "C17") (pin "1") (pinfunction "1_1") (pintype "passive"))
      (node (ref "R23") (pin "2") (pinfunction "2_2") (pintype "passive"))
      (node (ref "SENSOR") (pin "F29") (pinfunction "VRAMP2_F29") (pintype "bidirectional"))
    )
    (net (code "260") (name "VTREF") (class "Default")
      (node (ref "C65") (pin "1") (pinfunction "1_1") (pintype "passive"))
      (node (ref "C91") (pin "2") (pinfunction "2_2") (pintype "passive"))
      (node (ref "R21") (pin "2") (pinfunction "2_2") (pintype "passive"))
      (node (ref "R24") (pin "1") (pinfunction "1_1") (pintype "passive"))
      (node (ref "SENSOR") (pin "B2") (pinfunction "VTREF_B2") (pintype "bidirectional"))
      (node (ref "U3") (pin "4") (pinfunction "OUT_4") (pintype "power_in"))
    )
    (net (code "261") (name "VTSIG") (class "Default")
      (node (ref "C66") (pin "1") (pinfunction "1_1") (pintype "passive"))
      (node (ref "R24") (pin "2") (pinfunction "2_2") (pintype "passive"))
      (node (ref "SENSOR") (pin "C2") (pinfunction "VTSIG_C2") (pintype "bidirectional"))
    )
    (net (code "262") (name "unconnected-(U1-NC-Pad2)") (class "Default")
      (node (ref "U1") (pin "2") (pinfunction "NC_2") (pintype "no_connect"))
    )
    (net (code "263") (name "unconnected-(U1-NC-Pad4)") (class "Default")
      (node (ref "U1") (pin "4") (pinfunction "NC_4") (pintype "no_connect"))
    )
    (net (code "264") (name "unconnected-(U1-NC-Pad5)") (class "Default")
      (node (ref "U1") (pin "5") (pinfunction "NC_5") (pintype "no_connect"))
    )
    (net (code "265") (name "unconnected-(U2-NC-Pad2)") (class "Default")
      (node (ref "U2") (pin "2") (pinfunction "NC_2") (pintype "no_connect"))
    )
    (net (code "266") (name "unconnected-(U2-NC-Pad4)") (class "Default")
      (node (ref "U2") (pin "4") (pinfunction "NC_4") (pintype "no_connect"))
    )
    (net (code "267") (name "unconnected-(U2-NC-Pad5)") (class "Default")
      (node (ref "U2") (pin "5") (pinfunction "NC_5") (pintype "no_connect"))
    )
    (net (code "268") (name "unconnected-(U7-OS-Pad3)") (class "Default")
      (node (ref "U7") (pin "3") (pinfunction "OS_3") (pintype "output"))
    )
    (net (code "269") (name "unconnected-(X-NORTH-PadM1)") (class "Default")
      (node (ref "X-NORTH") (pin "M1") (pinfunction "M1_M1") (pintype "bidirectional"))
    )
    (net (code "270") (name "unconnected-(X-NORTH-PadM2)") (class "Default")
      (node (ref "X-NORTH") (pin "M2") (pinfunction "M2_M2") (pintype "bidirectional"))
    )
    (net (code "271") (name "unconnected-(X-SOUTH-PadM1)") (class "Default")
      (node (ref "X-SOUTH") (pin "M1") (pinfunction "M1_M1") (pintype "bidirectional"))
    )
    (net (code "272") (name "unconnected-(X-SOUTH-PadM2)") (class "Default")
      (node (ref "X-SOUTH") (pin "M2") (pinfunction "M2_M2") (pintype "bidirectional"))
    )
  )
)
